# cSTER_Space_Robotic_Arm_Schematic.net
KiCad netlist of a schematic drawn in EAGLE
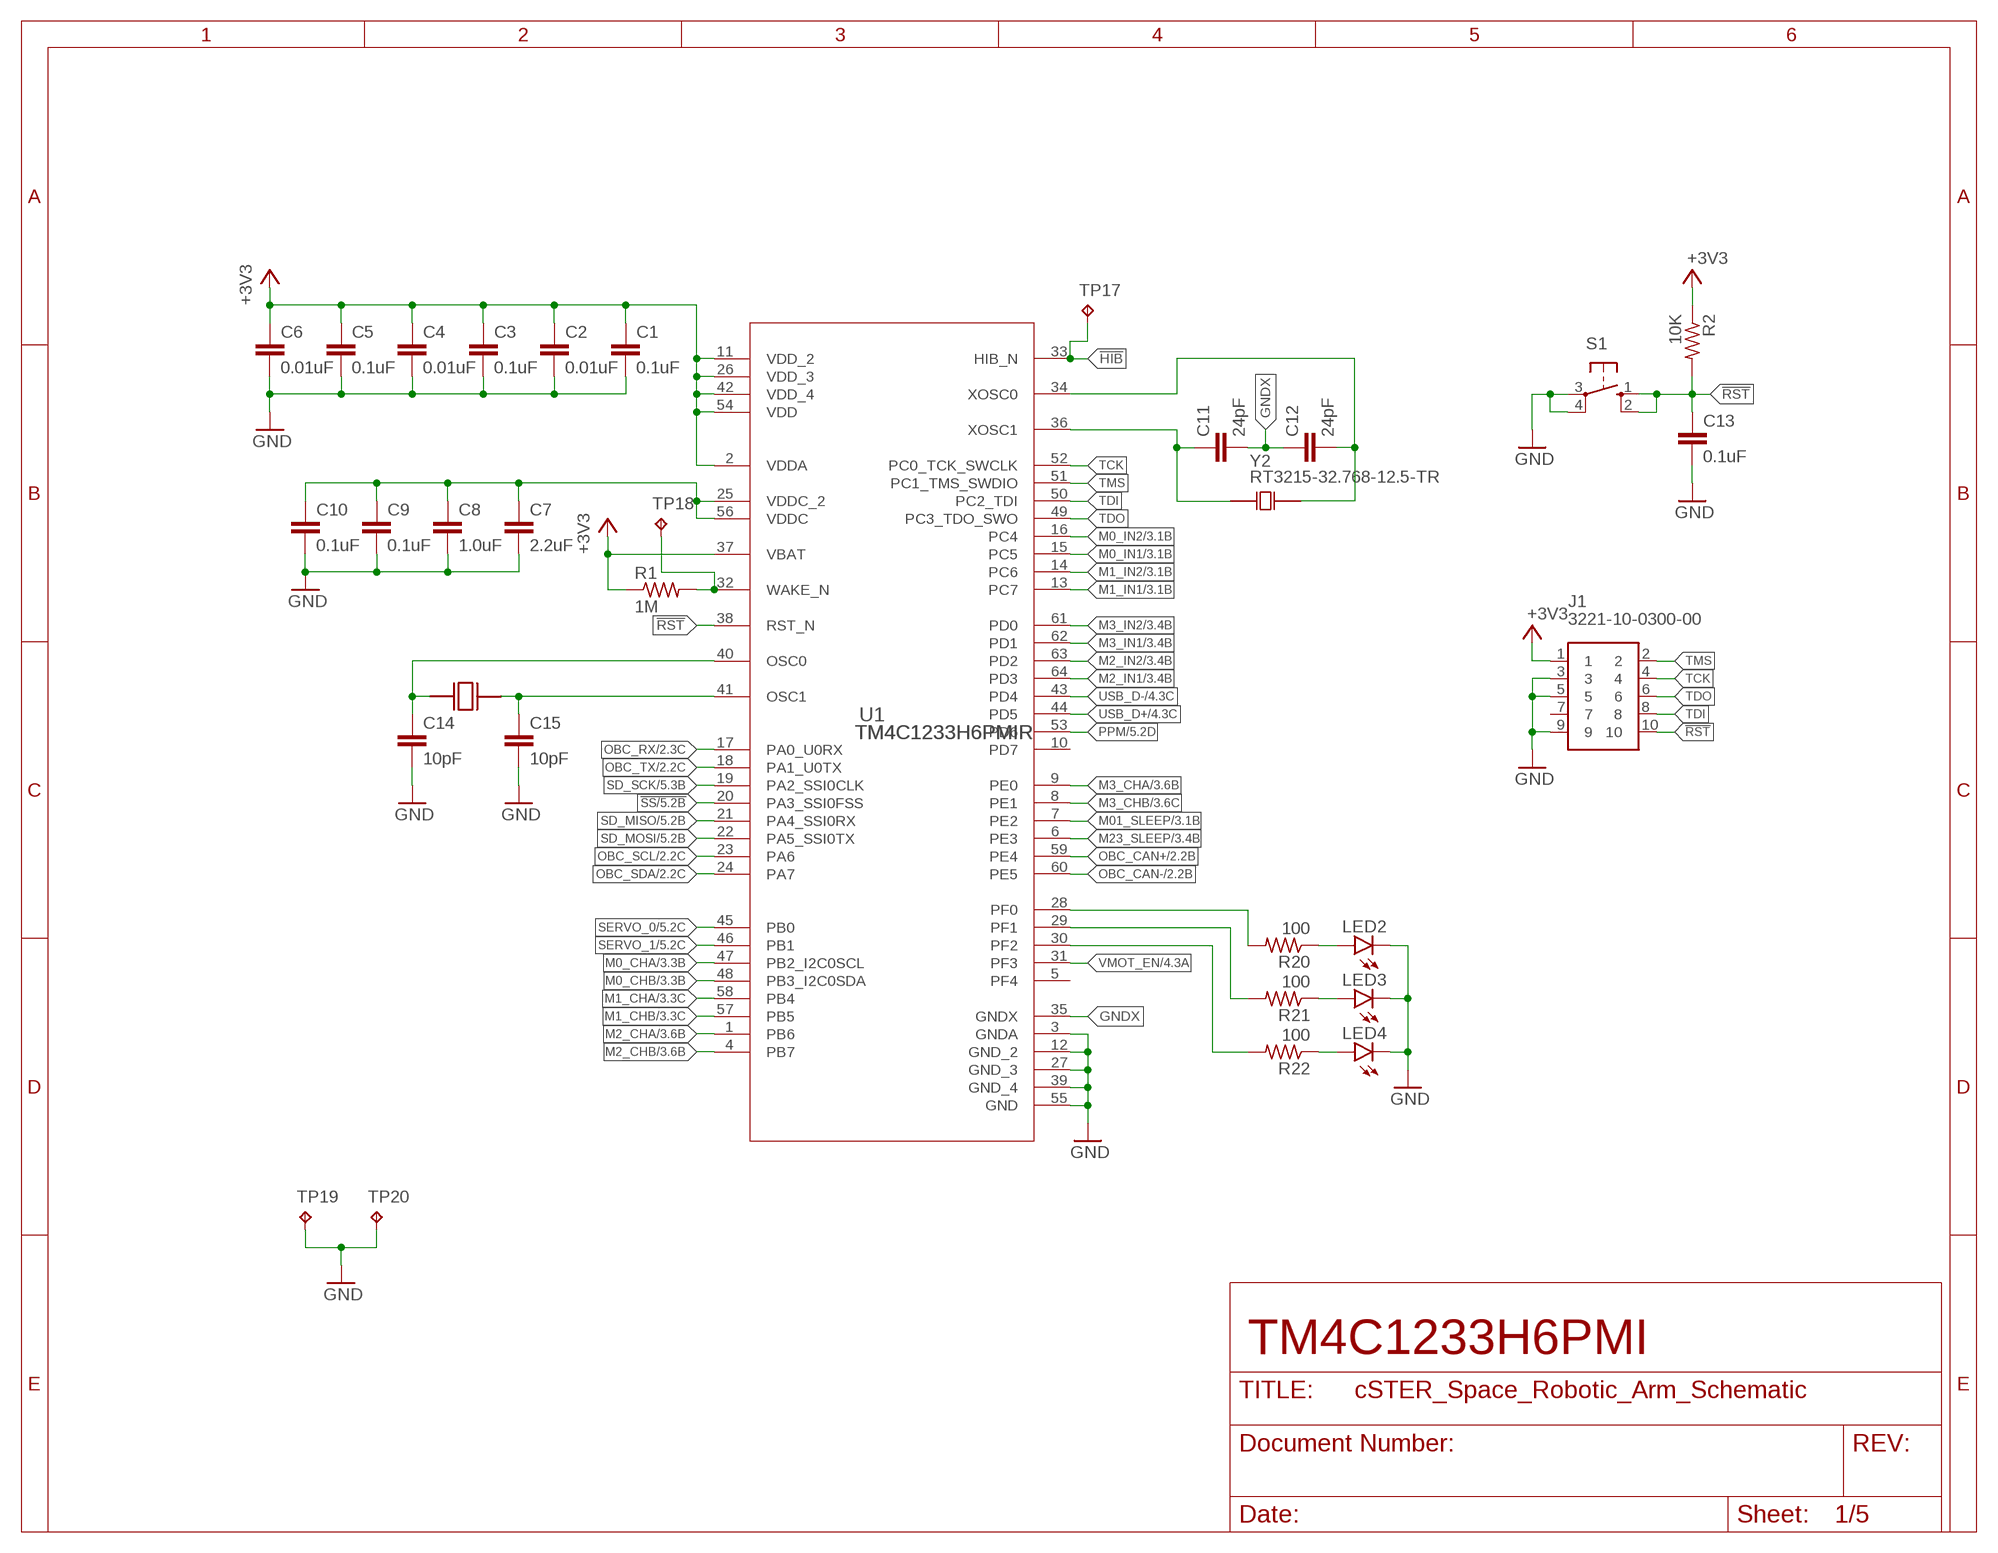
[diagram p0: schematic, sheet 1]
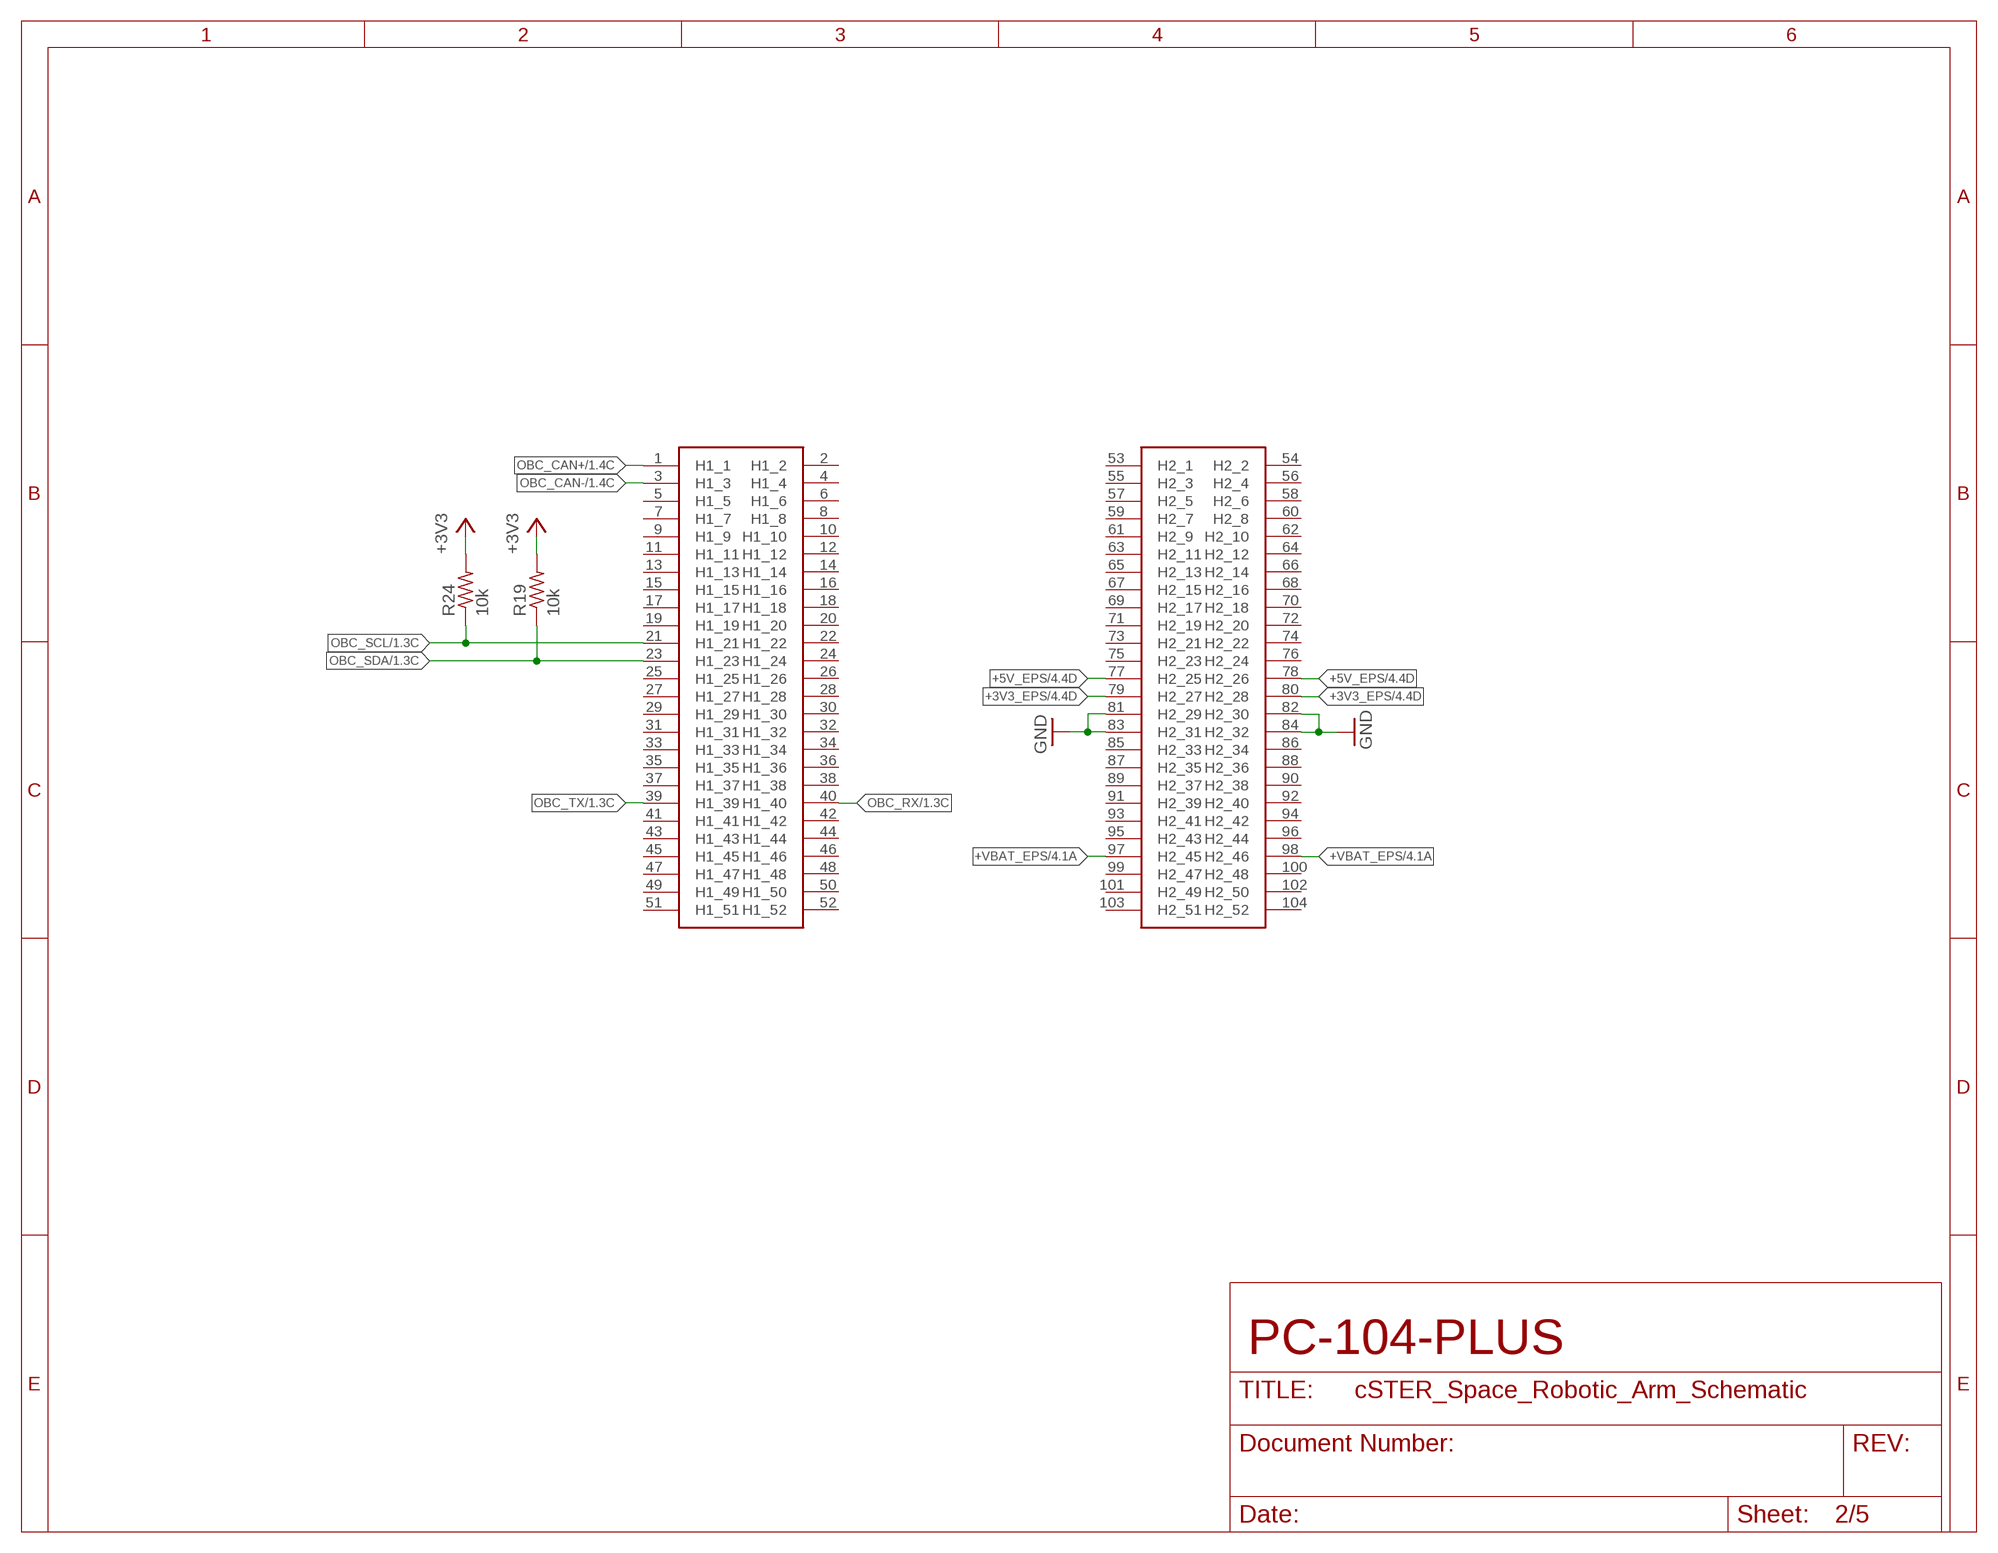
[diagram p1: schematic, sheet 2]
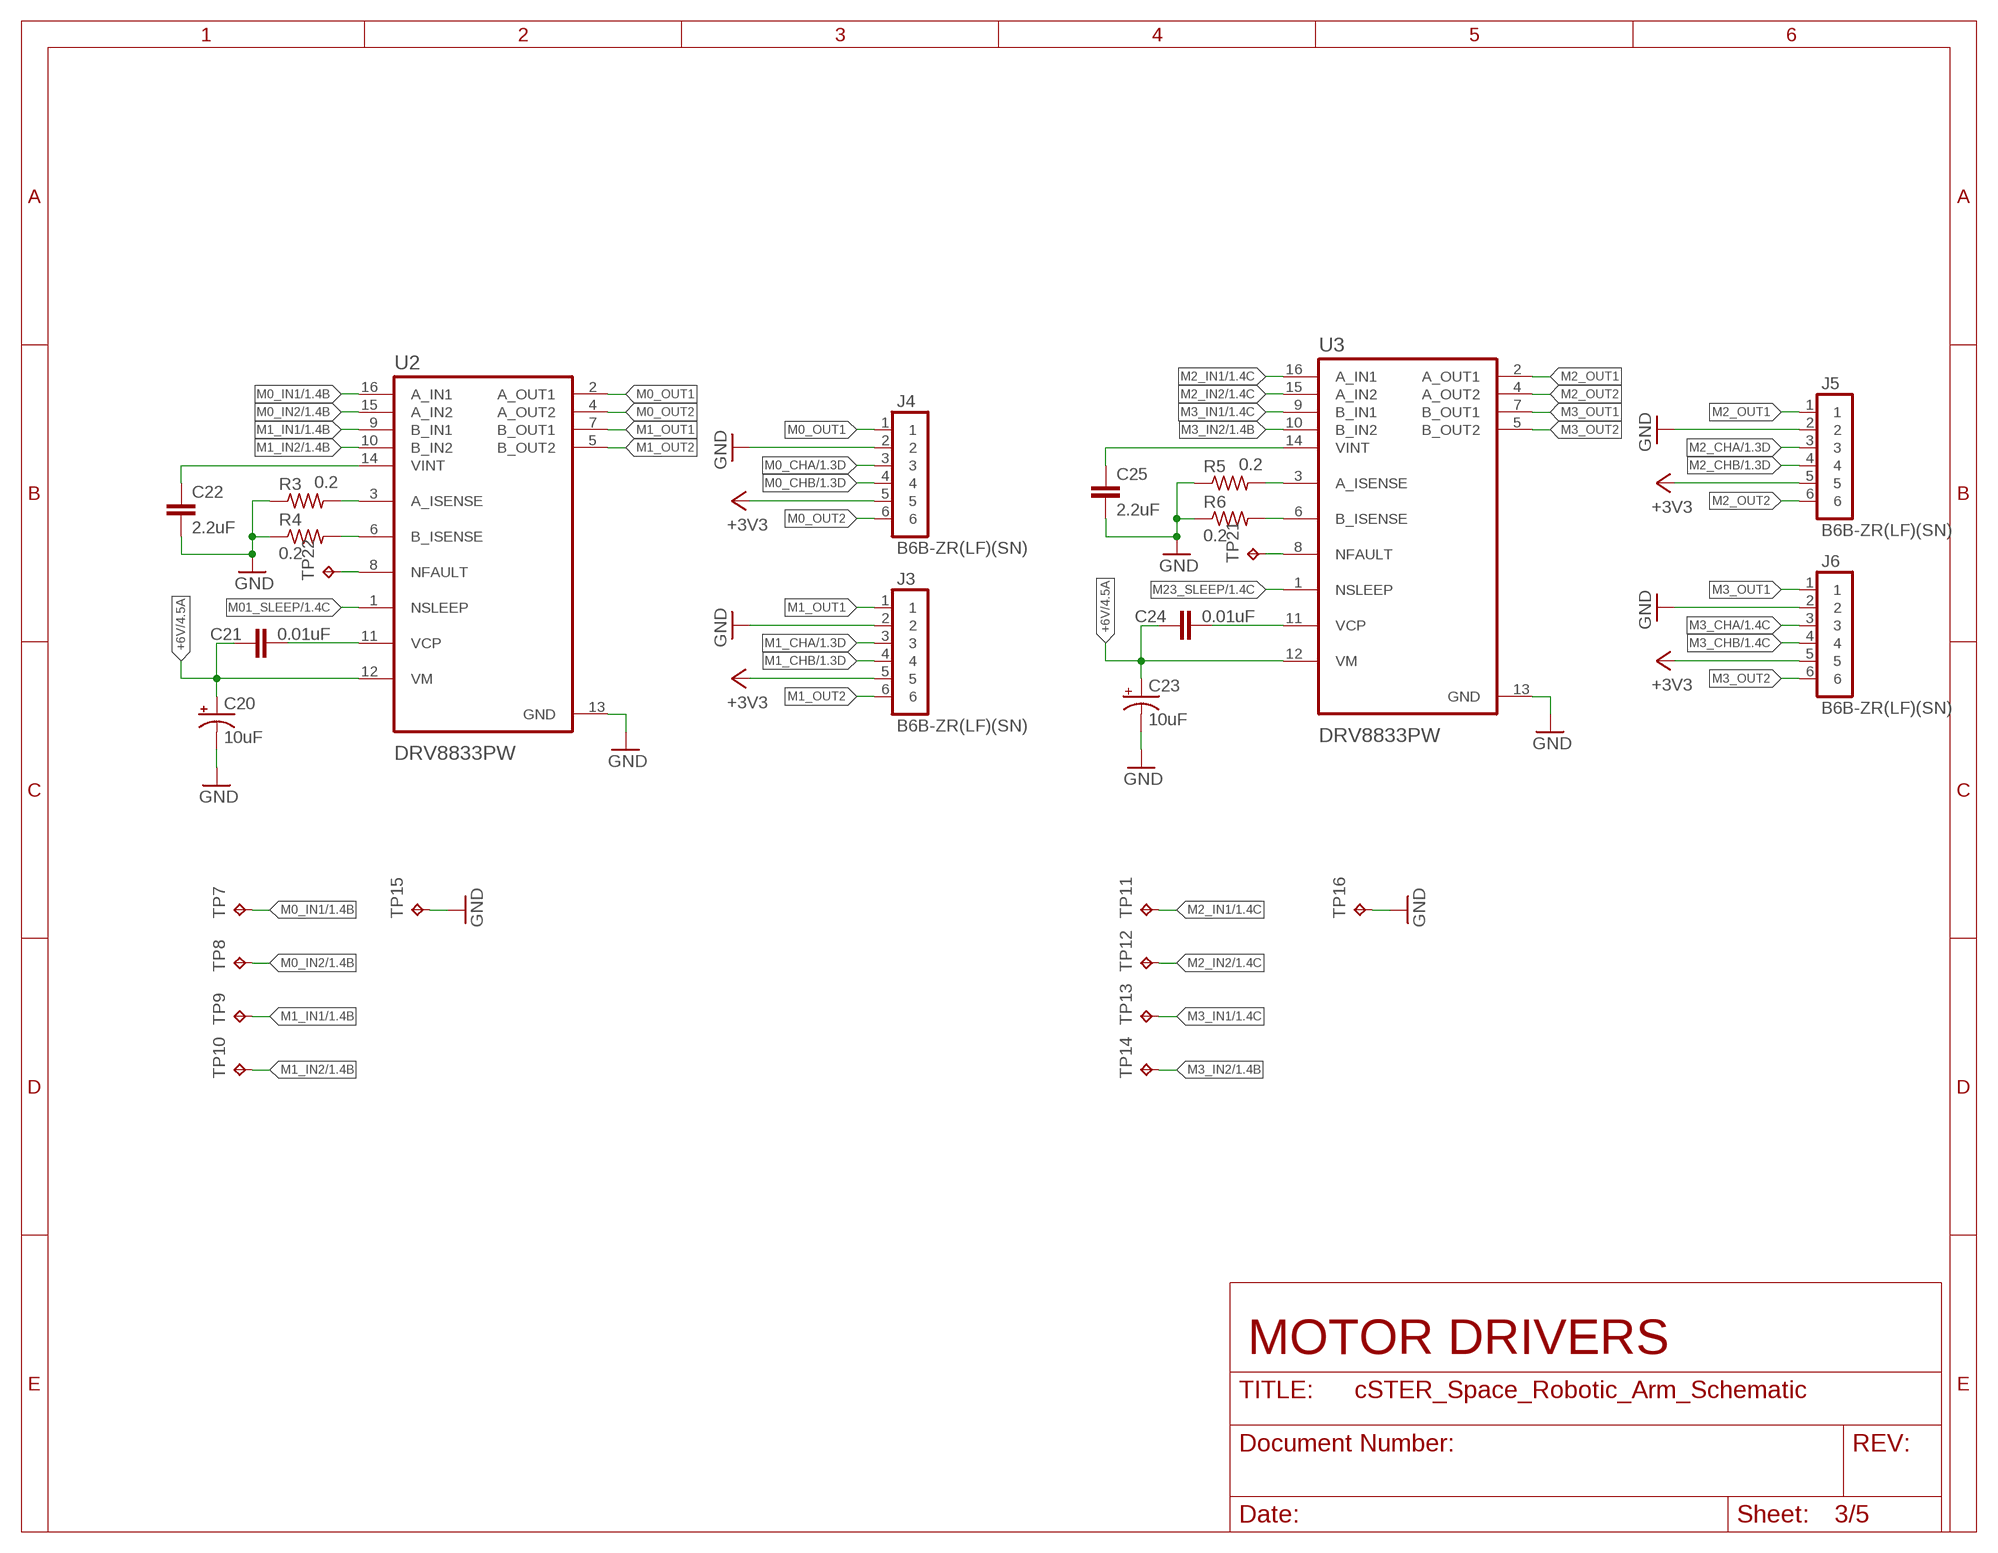
[diagram p2: schematic, sheet 3]
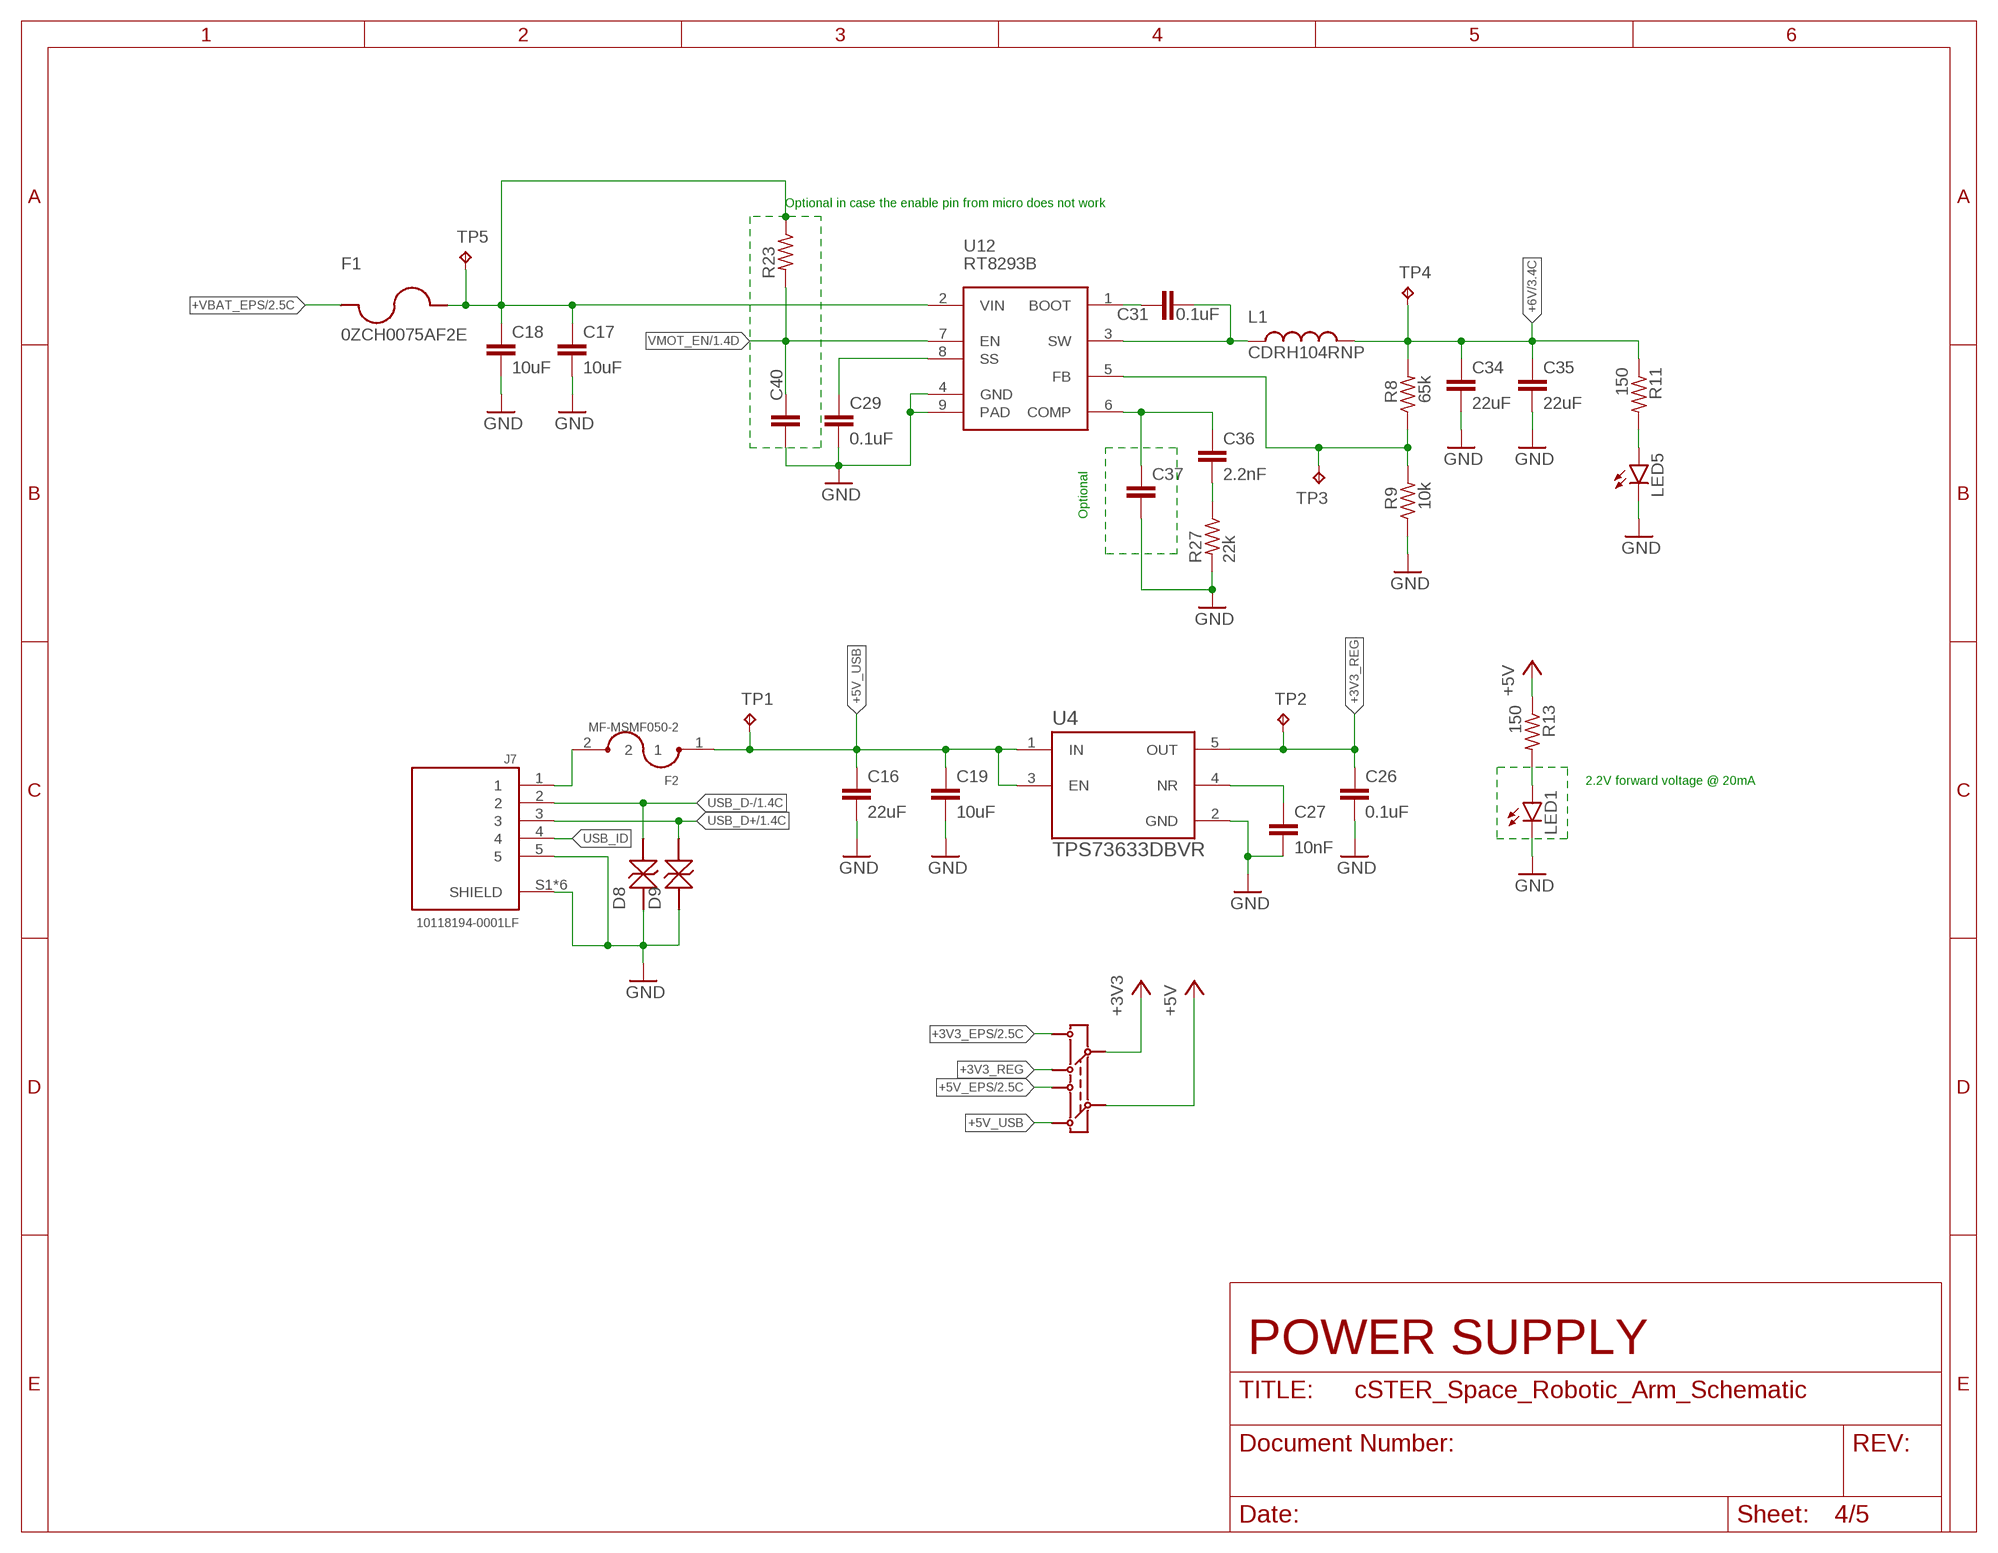
[diagram p3: schematic, sheet 4]
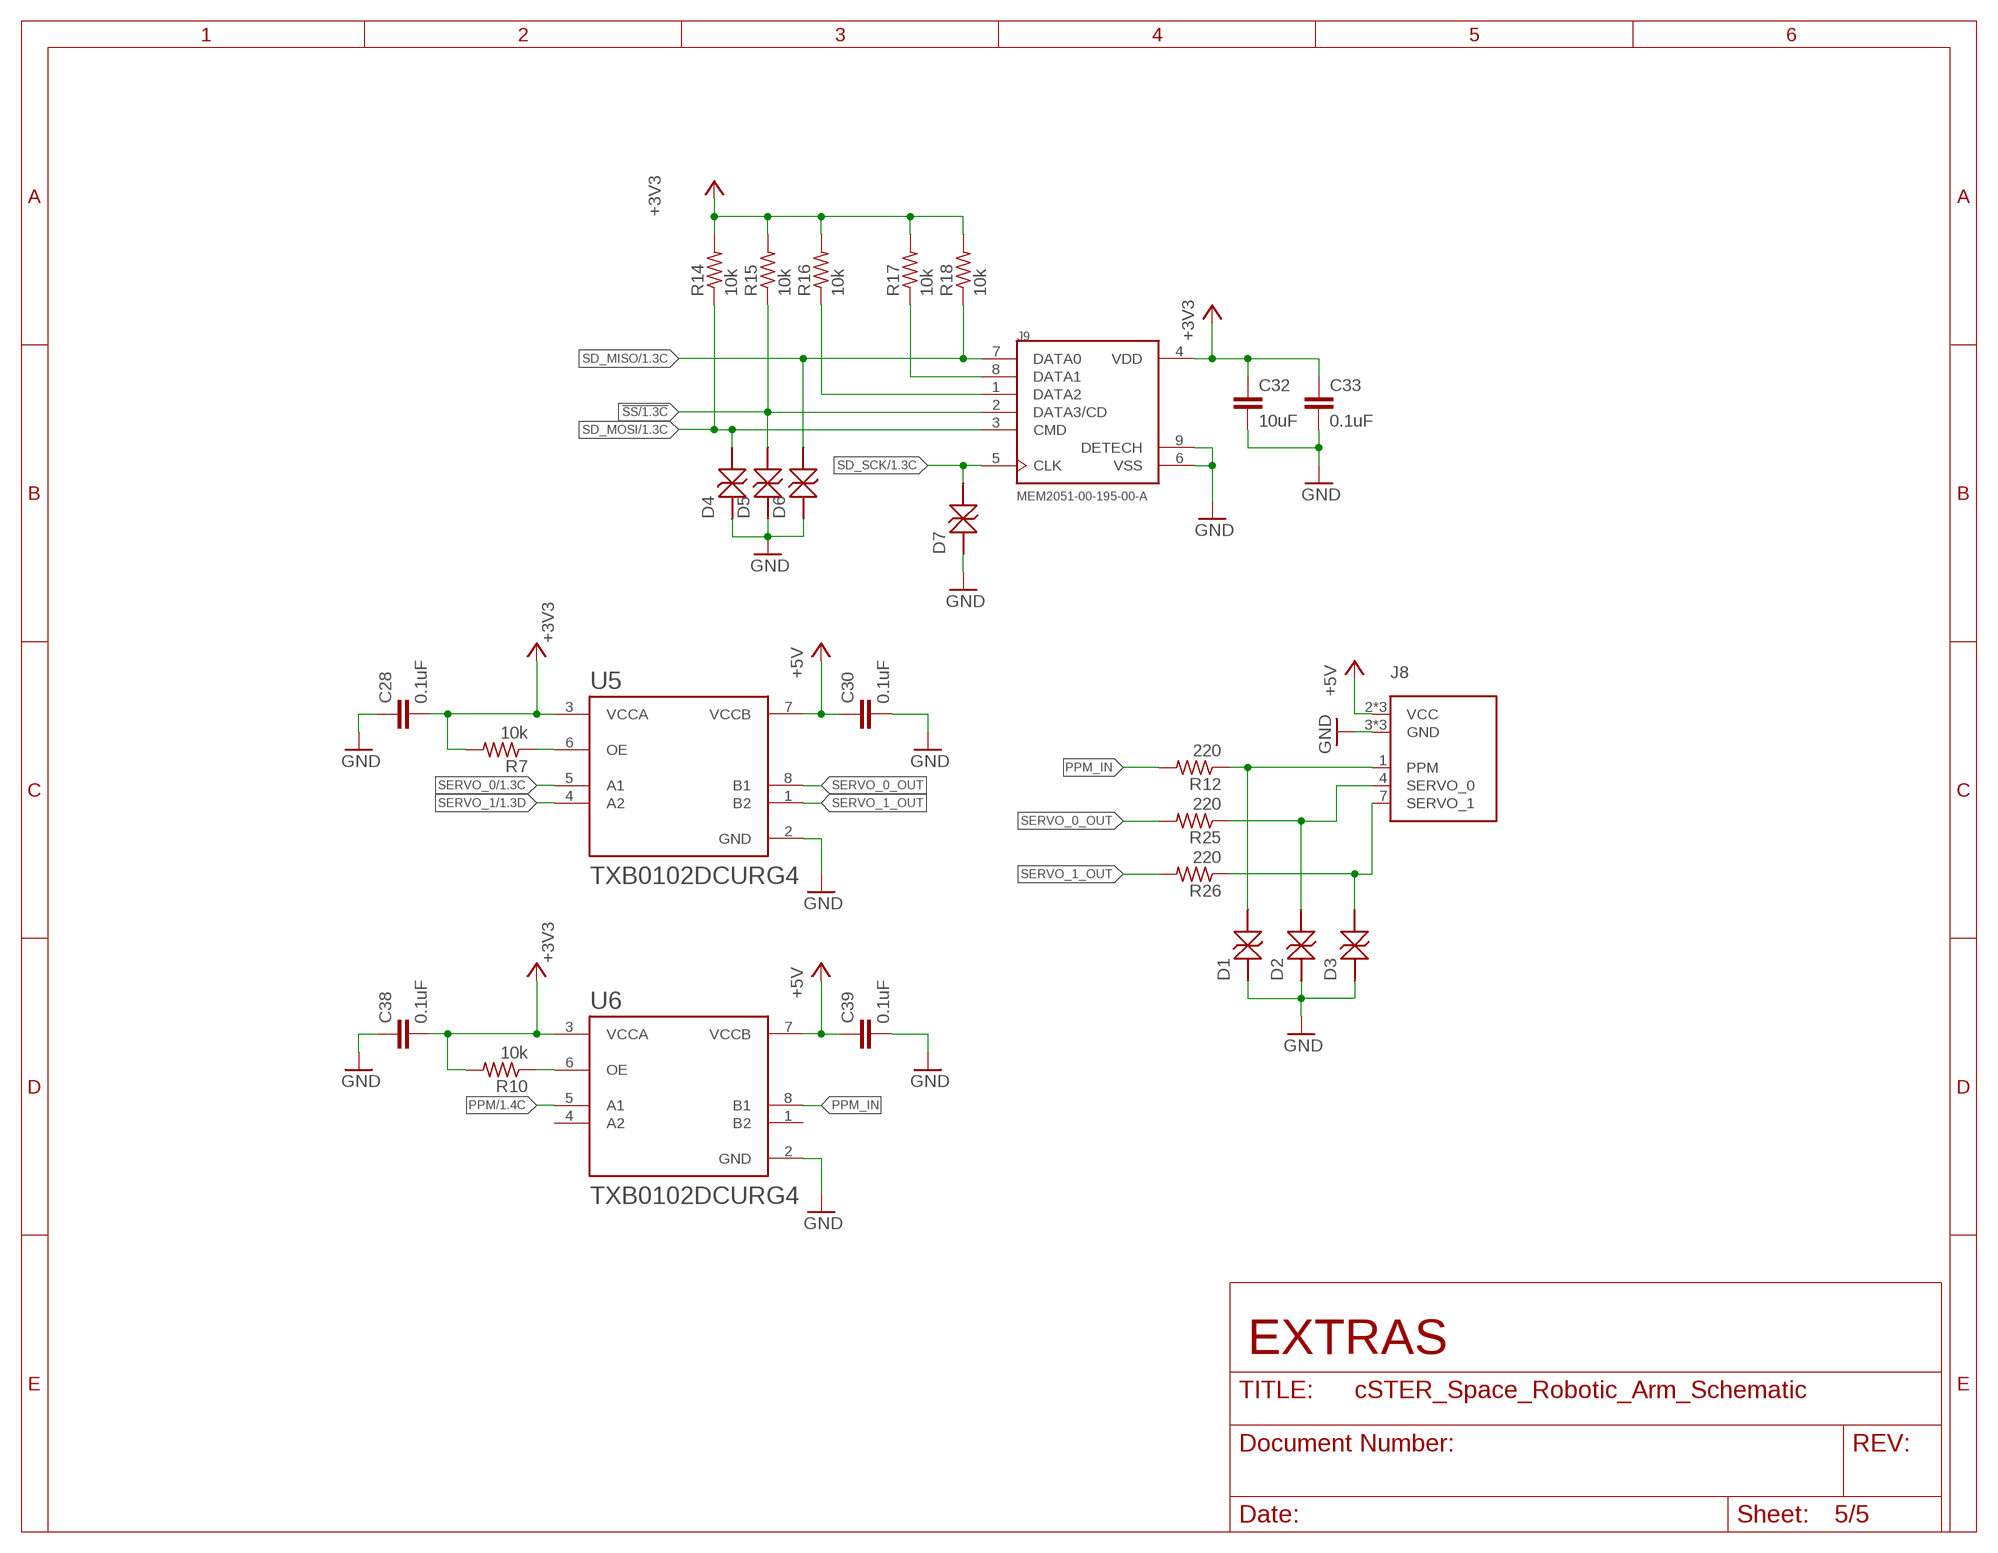
[diagram p4: schematic, sheet 5]

(export (version "E")
  (design (tool "Eeschema 10.0.6"))
  (components
    (comp (ref "C16")
      (value "22uF")
      (footprint "eagle-import:C1206")
      (libsource (lib "eagle-import") (part "C-EUC1206"))
    )
    (comp (ref "C17")
      (value "10uF")
      (footprint "eagle-import:C1206")
      (libsource (lib "eagle-import") (part "C-EUC1206"))
    )
    (comp (ref "C18")
      (value "10uF")
      (footprint "eagle-import:C1206")
      (libsource (lib "eagle-import") (part "C-EUC1206"))
    )
    (comp (ref "C19")
      (value "10uF")
      (footprint "eagle-import:C0603")
      (libsource (lib "eagle-import") (part "C-EUC0603"))
    )
    (comp (ref "C26")
      (value "0.1uF")
      (footprint "eagle-import:C0603")
      (libsource (lib "eagle-import") (part "C-EUC0603"))
    )
    (comp (ref "C27")
      (value "10nF")
      (footprint "eagle-import:C0603")
      (libsource (lib "eagle-import") (part "C-EUC0603"))
    )
    (comp (ref "C29")
      (value "0.1uF")
      (footprint "eagle-import:C0603")
      (libsource (lib "eagle-import") (part "C-EUC0603"))
    )
    (comp (ref "C31")
      (value "0.1uF")
      (footprint "eagle-import:C0603")
      (libsource (lib "eagle-import") (part "C-EUC0603"))
    )
    (comp (ref "C34")
      (value "22uF")
      (footprint "eagle-import:C1206")
      (libsource (lib "eagle-import") (part "C-EUC1206"))
    )
    (comp (ref "C35")
      (value "22uF")
      (footprint "eagle-import:C1206")
      (libsource (lib "eagle-import") (part "C-EUC1206"))
    )
    (comp (ref "C36")
      (value "2.2nF")
      (footprint "eagle-import:C0603")
      (libsource (lib "eagle-import") (part "C-EUC0603"))
    )
    (comp (ref "C37")
      (value "C-EUC0603")
      (footprint "eagle-import:C0603")
      (libsource (lib "eagle-import") (part "C-EUC0603"))
    )
    (comp (ref "C40")
      (value "C-EUC0603")
      (footprint "eagle-import:C0603")
      (libsource (lib "eagle-import") (part "C-EUC0603"))
    )
    (comp (ref "D8")
      (value "CPDQC5V0R")
      (footprint "eagle-import:CPDQC5V0R")
      (libsource (lib "eagle-import") (part "CPDQC5V0R"))
    )
    (comp (ref "D9")
      (value "CPDQC5V0R")
      (footprint "eagle-import:CPDQC5V0R")
      (libsource (lib "eagle-import") (part "CPDQC5V0R"))
    )
    (comp (ref "F1")
      (value "0ZCH0075AF2E")
      (footprint "eagle-import:0ZCH0075AF2E")
      (libsource (lib "eagle-import") (part "0ZCH0075AF2E"))
    )
    (comp (ref "F2")
      (value "MF-MSMF050-2")
      (footprint "eagle-import:FUSM4632X85")
      (fields (field (name "DIGI-KEY_PART_NUMBER") "MF-MSMF050-2CT-ND") (field (name "MF") "Bourns"))
      (libsource (lib "eagle-import") (part "MF-MSMF050-2"))
    )
    (comp (ref "J7")
      (value "10118194-0001LF")
      (footprint "eagle-import:AMPHENOL_10118194-0001LF")
      (fields (field (name "DIGI-KEY_PART_NUMBER") "609-4618-1-ND") (field (name "MF") "Amphenol ICC (FCI)"))
      (libsource (lib "eagle-import") (part "10118194-0001LF"))
    )
    (comp (ref "L1")
      (value "CDRH104RNP")
      (footprint "eagle-import:CDRH104RNP")
      (libsource (lib "eagle-import") (part "CDRH104RNP"))
    )
    (comp (ref "LED1")
      (value "LEDCHIPLED_0805")
      (footprint "eagle-import:CHIPLED_0805")
      (libsource (lib "eagle-import") (part "LEDCHIPLED_0805"))
    )
    (comp (ref "LED5")
      (value "LEDCHIPLED_0805")
      (footprint "eagle-import:CHIPLED_0805")
      (libsource (lib "eagle-import") (part "LEDCHIPLED_0805"))
    )
    (comp (ref "R8")
      (value "65k")
      (footprint "eagle-import:R0603")
      (libsource (lib "eagle-import") (part "R-US_R0603"))
    )
    (comp (ref "R9")
      (value "10k")
      (footprint "eagle-import:R0603")
      (libsource (lib "eagle-import") (part "R-US_R0603"))
    )
    (comp (ref "R11")
      (value "150")
      (footprint "eagle-import:R0603")
      (libsource (lib "eagle-import") (part "R-US_R0603"))
    )
    (comp (ref "R13")
      (value "150")
      (footprint "eagle-import:R0603")
      (libsource (lib "eagle-import") (part "R-US_R0603"))
    )
    (comp (ref "R23")
      (value "R-US_R0603")
      (footprint "eagle-import:R0603")
      (libsource (lib "eagle-import") (part "R-US_R0603"))
    )
    (comp (ref "R27")
      (value "22k")
      (footprint "eagle-import:R0603")
      (libsource (lib "eagle-import") (part "R-US_R0603"))
    )
    (comp (ref "TP1")
      (value "TPPAD1-13")
      (footprint "eagle-import:P1-13")
      (libsource (lib "eagle-import") (part "TPPAD1-13"))
    )
    (comp (ref "TP2")
      (value "TPPAD1-13")
      (footprint "eagle-import:P1-13")
      (libsource (lib "eagle-import") (part "TPPAD1-13"))
    )
    (comp (ref "TP3")
      (value "TPPAD1-13")
      (footprint "eagle-import:P1-13")
      (libsource (lib "eagle-import") (part "TPPAD1-13"))
    )
    (comp (ref "TP4")
      (value "TPPAD1-13")
      (footprint "eagle-import:P1-13")
      (libsource (lib "eagle-import") (part "TPPAD1-13"))
    )
    (comp (ref "TP5")
      (value "TPPAD1-13")
      (footprint "eagle-import:P1-13")
      (libsource (lib "eagle-import") (part "TPPAD1-13"))
    )
    (comp (ref "U$1")
      (value "JS202011CQN")
      (footprint "eagle-import:JS202011CQN")
      (libsource (lib "eagle-import") (part "JS202011CQN"))
    )
    (comp (ref "U4")
      (value "TPS73633DBVR")
      (footprint "eagle-import:SOT95P280X145-5N")
      (fields (field (name "DIGI-KEY_PART_NUMBER") "296-27064-1-ND") (field (name "MF") "Texas Instruments"))
      (libsource (lib "eagle-import") (part "TPS73633DBVR"))
    )
    (comp (ref "U12")
      (value "RT8293B")
      (footprint "eagle-import:RT8293B")
      (libsource (lib "eagle-import") (part "RT8293B"))
    )
    (comp (ref "C20")
      (value "10uF")
      (footprint "eagle-import:CT3216")
      (libsource (lib "eagle-import") (part "CPOL-USCT3216"))
    )
    (comp (ref "C21")
      (value "0.01uF")
      (footprint "eagle-import:C0805")
      (libsource (lib "eagle-import") (part "C-EUC0805"))
    )
    (comp (ref "C22")
      (value "2.2uF")
      (footprint "eagle-import:C0603")
      (libsource (lib "eagle-import") (part "C-EUC0603"))
    )
    (comp (ref "C23")
      (value "10uF")
      (footprint "eagle-import:CT3216")
      (libsource (lib "eagle-import") (part "CPOL-USCT3216"))
    )
    (comp (ref "C24")
      (value "0.01uF")
      (footprint "eagle-import:C0805")
      (libsource (lib "eagle-import") (part "C-EUC0805"))
    )
    (comp (ref "C25")
      (value "2.2uF")
      (footprint "eagle-import:C0603")
      (libsource (lib "eagle-import") (part "C-EUC0603"))
    )
    (comp (ref "J3")
      (value "B6B-ZR(LF)(SN)")
      (footprint "eagle-import:JST_B6B-ZR(LF)(SN)")
      (fields (field (name "DIGI-KEY_PART_NUMBER") "455-1661-ND") (field (name "MF") "JST Sales"))
      (libsource (lib "eagle-import") (part "B6B-ZR(LF)(SN)"))
    )
    (comp (ref "J4")
      (value "B6B-ZR(LF)(SN)")
      (footprint "eagle-import:JST_B6B-ZR(LF)(SN)")
      (fields (field (name "DIGI-KEY_PART_NUMBER") "455-1661-ND") (field (name "MF") "JST Sales"))
      (libsource (lib "eagle-import") (part "B6B-ZR(LF)(SN)"))
    )
    (comp (ref "J5")
      (value "B6B-ZR(LF)(SN)")
      (footprint "eagle-import:JST_B6B-ZR(LF)(SN)")
      (fields (field (name "DIGI-KEY_PART_NUMBER") "455-1661-ND") (field (name "MF") "JST Sales"))
      (libsource (lib "eagle-import") (part "B6B-ZR(LF)(SN)"))
    )
    (comp (ref "J6")
      (value "B6B-ZR(LF)(SN)")
      (footprint "eagle-import:JST_B6B-ZR(LF)(SN)")
      (fields (field (name "DIGI-KEY_PART_NUMBER") "455-1661-ND") (field (name "MF") "JST Sales"))
      (libsource (lib "eagle-import") (part "B6B-ZR(LF)(SN)"))
    )
    (comp (ref "R3")
      (value "0.2")
      (footprint "eagle-import:R1206")
      (libsource (lib "eagle-import") (part "R-US_R1206"))
    )
    (comp (ref "R4")
      (value "0.2")
      (footprint "eagle-import:R1206")
      (libsource (lib "eagle-import") (part "R-US_R1206"))
    )
    (comp (ref "R5")
      (value "0.2")
      (footprint "eagle-import:R1206")
      (libsource (lib "eagle-import") (part "R-US_R1206"))
    )
    (comp (ref "R6")
      (value "0.2")
      (footprint "eagle-import:R1206")
      (libsource (lib "eagle-import") (part "R-US_R1206"))
    )
    (comp (ref "TP7")
      (value "TPPAD1-13")
      (footprint "eagle-import:P1-13")
      (libsource (lib "eagle-import") (part "TPPAD1-13"))
    )
    (comp (ref "TP8")
      (value "TPPAD1-13")
      (footprint "eagle-import:P1-13")
      (libsource (lib "eagle-import") (part "TPPAD1-13"))
    )
    (comp (ref "TP9")
      (value "TPPAD1-13")
      (footprint "eagle-import:P1-13")
      (libsource (lib "eagle-import") (part "TPPAD1-13"))
    )
    (comp (ref "TP10")
      (value "TPPAD1-13")
      (footprint "eagle-import:P1-13")
      (libsource (lib "eagle-import") (part "TPPAD1-13"))
    )
    (comp (ref "TP11")
      (value "TPPAD1-13")
      (footprint "eagle-import:P1-13")
      (libsource (lib "eagle-import") (part "TPPAD1-13"))
    )
    (comp (ref "TP12")
      (value "TPPAD1-13")
      (footprint "eagle-import:P1-13")
      (libsource (lib "eagle-import") (part "TPPAD1-13"))
    )
    (comp (ref "TP13")
      (value "TPPAD1-13")
      (footprint "eagle-import:P1-13")
      (libsource (lib "eagle-import") (part "TPPAD1-13"))
    )
    (comp (ref "TP14")
      (value "TPPAD1-13")
      (footprint "eagle-import:P1-13")
      (libsource (lib "eagle-import") (part "TPPAD1-13"))
    )
    (comp (ref "TP15")
      (value "TPPAD1-13")
      (footprint "eagle-import:P1-13")
      (libsource (lib "eagle-import") (part "TPPAD1-13"))
    )
    (comp (ref "TP16")
      (value "TPPAD1-13")
      (footprint "eagle-import:P1-13")
      (libsource (lib "eagle-import") (part "TPPAD1-13"))
    )
    (comp (ref "TP21")
      (value "TPPAD1-13")
      (footprint "eagle-import:P1-13")
      (libsource (lib "eagle-import") (part "TPPAD1-13"))
    )
    (comp (ref "TP22")
      (value "TPPAD1-13")
      (footprint "eagle-import:P1-13")
      (libsource (lib "eagle-import") (part "TPPAD1-13"))
    )
    (comp (ref "U2")
      (value "DRV8833PW")
      (footprint "eagle-import:SOP65P640X120-16N")
      (fields (field (name "DIGI-KEY_PART_NUMBER") "296-29394-5-ND") (field (name "MF") "Texas Instruments"))
      (libsource (lib "eagle-import") (part "DRV8833PW"))
    )
    (comp (ref "U3")
      (value "DRV8833PW")
      (footprint "eagle-import:SOP65P640X120-16N")
      (fields (field (name "DIGI-KEY_PART_NUMBER") "296-29394-5-ND") (field (name "MF") "Texas Instruments"))
      (libsource (lib "eagle-import") (part "DRV8833PW"))
    )
    (comp (ref "C28")
      (value "0.1uF")
      (footprint "eagle-import:C0402K")
      (libsource (lib "eagle-import") (part "C-EUC0402K"))
    )
    (comp (ref "C30")
      (value "0.1uF")
      (footprint "eagle-import:C0402K")
      (libsource (lib "eagle-import") (part "C-EUC0402K"))
    )
    (comp (ref "C32")
      (value "10uF")
      (footprint "eagle-import:C0603")
      (libsource (lib "eagle-import") (part "C-EUC0603"))
    )
    (comp (ref "C33")
      (value "0.1uF")
      (footprint "eagle-import:C0603")
      (libsource (lib "eagle-import") (part "C-EUC0603"))
    )
    (comp (ref "C38")
      (value "0.1uF")
      (footprint "eagle-import:C0402K")
      (libsource (lib "eagle-import") (part "C-EUC0402K"))
    )
    (comp (ref "C39")
      (value "0.1uF")
      (footprint "eagle-import:C0402K")
      (libsource (lib "eagle-import") (part "C-EUC0402K"))
    )
    (comp (ref "D1")
      (value "CPDQC5V0R")
      (footprint "eagle-import:CPDQC5V0R")
      (libsource (lib "eagle-import") (part "CPDQC5V0R"))
    )
    (comp (ref "D2")
      (value "CPDQC5V0R")
      (footprint "eagle-import:CPDQC5V0R")
      (libsource (lib "eagle-import") (part "CPDQC5V0R"))
    )
    (comp (ref "D3")
      (value "CPDQC5V0R")
      (footprint "eagle-import:CPDQC5V0R")
      (libsource (lib "eagle-import") (part "CPDQC5V0R"))
    )
    (comp (ref "D4")
      (value "CPDQC5V0R")
      (footprint "eagle-import:CPDQC5V0R")
      (libsource (lib "eagle-import") (part "CPDQC5V0R"))
    )
    (comp (ref "D5")
      (value "CPDQC5V0R")
      (footprint "eagle-import:CPDQC5V0R")
      (libsource (lib "eagle-import") (part "CPDQC5V0R"))
    )
    (comp (ref "D6")
      (value "CPDQC5V0R")
      (footprint "eagle-import:CPDQC5V0R")
      (libsource (lib "eagle-import") (part "CPDQC5V0R"))
    )
    (comp (ref "D7")
      (value "CPDQC5V0R")
      (footprint "eagle-import:CPDQC5V0R")
      (libsource (lib "eagle-import") (part "CPDQC5V0R"))
    )
    (comp (ref "J8")
      (value "ROBOT_PORT")
      (footprint "eagle-import:ROBOT_PORT")
      (libsource (lib "eagle-import") (part "ROBOT_PORT"))
    )
    (comp (ref "J9")
      (value "MEM2051-00-195-00-A")
      (footprint "eagle-import:GCT_MEM2051-00-195-00-A")
      (fields (field (name "MF") "Global Connector Technology"))
      (libsource (lib "eagle-import") (part "MEM2051-00-195-00-A"))
    )
    (comp (ref "R7")
      (value "10k")
      (footprint "eagle-import:R0402")
      (libsource (lib "eagle-import") (part "R-US_R0402"))
    )
    (comp (ref "R10")
      (value "10k")
      (footprint "eagle-import:R0402")
      (libsource (lib "eagle-import") (part "R-US_R0402"))
    )
    (comp (ref "R12")
      (value "220")
      (footprint "eagle-import:R0603")
      (libsource (lib "eagle-import") (part "R-US_R0603"))
    )
    (comp (ref "R14")
      (value "10k")
      (footprint "eagle-import:R0603")
      (libsource (lib "eagle-import") (part "R-US_R0603"))
    )
    (comp (ref "R15")
      (value "10k")
      (footprint "eagle-import:R0603")
      (libsource (lib "eagle-import") (part "R-US_R0603"))
    )
    (comp (ref "R16")
      (value "10k")
      (footprint "eagle-import:R0603")
      (libsource (lib "eagle-import") (part "R-US_R0603"))
    )
    (comp (ref "R17")
      (value "10k")
      (footprint "eagle-import:R0603")
      (libsource (lib "eagle-import") (part "R-US_R0603"))
    )
    (comp (ref "R18")
      (value "10k")
      (footprint "eagle-import:R0603")
      (libsource (lib "eagle-import") (part "R-US_R0603"))
    )
    (comp (ref "R25")
      (value "220")
      (footprint "eagle-import:R0603")
      (libsource (lib "eagle-import") (part "R-US_R0603"))
    )
    (comp (ref "R26")
      (value "220")
      (footprint "eagle-import:R0603")
      (libsource (lib "eagle-import") (part "R-US_R0603"))
    )
    (comp (ref "U5")
      (value "TXB0102DCURG4")
      (footprint "eagle-import:SOP50P310X90-8N")
      (fields (field (name "DIGI-KEY_PART_NUMBER") "296-52836-2-ND") (field (name "MF") "Texas Instruments"))
      (libsource (lib "eagle-import") (part "TXB0102DCURG4"))
    )
    (comp (ref "U6")
      (value "TXB0102DCURG4")
      (footprint "eagle-import:SOP50P310X90-8N")
      (fields (field (name "DIGI-KEY_PART_NUMBER") "296-52836-2-ND") (field (name "MF") "Texas Instruments"))
      (libsource (lib "eagle-import") (part "TXB0102DCURG4"))
    )
    (comp (ref "C1")
      (value "0.1uF")
      (footprint "eagle-import:C0402K")
      (libsource (lib "eagle-import") (part "C-EUC0402K"))
    )
    (comp (ref "C2")
      (value "0.01uF")
      (footprint "eagle-import:C0402K")
      (libsource (lib "eagle-import") (part "C-EUC0402K"))
    )
    (comp (ref "C3")
      (value "0.1uF")
      (footprint "eagle-import:C0402K")
      (libsource (lib "eagle-import") (part "C-EUC0402K"))
    )
    (comp (ref "C4")
      (value "0.01uF")
      (footprint "eagle-import:C0402K")
      (libsource (lib "eagle-import") (part "C-EUC0402K"))
    )
    (comp (ref "C5")
      (value "0.1uF")
      (footprint "eagle-import:C0402K")
      (libsource (lib "eagle-import") (part "C-EUC0402K"))
    )
    (comp (ref "C6")
      (value "0.01uF")
      (footprint "eagle-import:C0402K")
      (libsource (lib "eagle-import") (part "C-EUC0402K"))
    )
    (comp (ref "C7")
      (value "2.2uF")
      (footprint "eagle-import:C0402K")
      (libsource (lib "eagle-import") (part "C-EUC0402K"))
    )
    (comp (ref "C8")
      (value "1.0uF")
      (footprint "eagle-import:C0402K")
      (libsource (lib "eagle-import") (part "C-EUC0402K"))
    )
    (comp (ref "C9")
      (value "0.1uF")
      (footprint "eagle-import:C0402K")
      (libsource (lib "eagle-import") (part "C-EUC0402K"))
    )
    (comp (ref "C10")
      (value "0.1uF")
      (footprint "eagle-import:C0402K")
      (libsource (lib "eagle-import") (part "C-EUC0402K"))
    )
    (comp (ref "C11")
      (value "24pF")
      (footprint "eagle-import:C0402K")
      (libsource (lib "eagle-import") (part "C-EUC0402K"))
    )
    (comp (ref "C12")
      (value "24pF")
      (footprint "eagle-import:C0402K")
      (libsource (lib "eagle-import") (part "C-EUC0402K"))
    )
    (comp (ref "C13")
      (value "0.1uF")
      (footprint "eagle-import:C0603")
      (libsource (lib "eagle-import") (part "C-EUC0603"))
    )
    (comp (ref "C14")
      (value "10pF")
      (footprint "eagle-import:C0402K")
      (libsource (lib "eagle-import") (part "C-EUC0402K"))
    )
    (comp (ref "C15")
      (value "10pF")
      (footprint "eagle-import:C0402K")
      (libsource (lib "eagle-import") (part "C-EUC0402K"))
    )
    (comp (ref "J1")
      (value "3221-10-0300-00")
      (footprint "eagle-import:3221-10-0300-00")
      (libsource (lib "eagle-import") (part "3221-10-0300-00"))
    )
    (comp (ref "LED2")
      (value "LEDCHIPLED_0805")
      (footprint "eagle-import:CHIPLED_0805")
      (libsource (lib "eagle-import") (part "LEDCHIPLED_0805"))
    )
    (comp (ref "LED3")
      (value "LEDCHIPLED_0805")
      (footprint "eagle-import:CHIPLED_0805")
      (libsource (lib "eagle-import") (part "LEDCHIPLED_0805"))
    )
    (comp (ref "LED4")
      (value "LEDCHIPLED_0805")
      (footprint "eagle-import:CHIPLED_0805")
      (libsource (lib "eagle-import") (part "LEDCHIPLED_0805"))
    )
    (comp (ref "R1")
      (value "1M")
      (footprint "eagle-import:R0402")
      (libsource (lib "eagle-import") (part "R-US_R0402"))
    )
    (comp (ref "R2")
      (value "10K")
      (footprint "eagle-import:R0603")
      (libsource (lib "eagle-import") (part "R-US_R0603"))
    )
    (comp (ref "R20")
      (value "100")
      (footprint "eagle-import:R0603")
      (libsource (lib "eagle-import") (part "R-US_R0603"))
    )
    (comp (ref "R21")
      (value "100")
      (footprint "eagle-import:R0603")
      (libsource (lib "eagle-import") (part "R-US_R0603"))
    )
    (comp (ref "R22")
      (value "100")
      (footprint "eagle-import:R0603")
      (libsource (lib "eagle-import") (part "R-US_R0603"))
    )
    (comp (ref "S1")
      (value "10-XX")
      (footprint "eagle-import:B3F-10XX")
      (fields (field (name "MPN") "B3F-1000"))
      (libsource (lib "eagle-import") (part "10-XX"))
    )
    (comp (ref "TP17")
      (value "TPPAD1-13")
      (footprint "eagle-import:P1-13")
      (libsource (lib "eagle-import") (part "TPPAD1-13"))
    )
    (comp (ref "TP18")
      (value "TPPAD1-13")
      (footprint "eagle-import:P1-13")
      (libsource (lib "eagle-import") (part "TPPAD1-13"))
    )
    (comp (ref "TP19")
      (value "TPPAD1-13")
      (footprint "eagle-import:P1-13")
      (libsource (lib "eagle-import") (part "TPPAD1-13"))
    )
    (comp (ref "TP20")
      (value "TPPAD1-13")
      (footprint "eagle-import:P1-13")
      (libsource (lib "eagle-import") (part "TPPAD1-13"))
    )
    (comp (ref "U1")
      (value "TM4C1233H6PMIR")
      (footprint "eagle-import:PM0064A_N")
      (fields (field (name "COPYRIGHT") "Copyright (C) 2021 Ultra Librarian. All rights reserved."))
      (libsource (lib "eagle-import") (part "TM4C1233H6PMIR"))
    )
    (comp (ref "Y1")
      (value "ECS-160-9-42-CKM-TR")
      (footprint "eagle-import:XTAL_ECS-160-9-42-CKM-TR")
      (fields (field (name "DIGI-KEY_PART_NUMBER") "XC1611CT-ND") (field (name "MF") "ECS Inc."))
      (libsource (lib "eagle-import") (part "ECS-160-9-42-CKM-TR"))
    )
    (comp (ref "Y2")
      (value "RT3215-32.768-12.5-TR")
      (footprint "eagle-import:RT3215-32.768-12.5-TR")
      (libsource (lib "eagle-import") (part "RT3215-32.768-12.5-TR"))
    )
    (comp (ref "J2")
      (value "PC-104-PLUS")
      (footprint "eagle-import:PC-104-PLUS")
      (libsource (lib "eagle-import") (part "PC-104-PLUS"))
    )
    (comp (ref "R19")
      (value "10k")
      (footprint "eagle-import:R0603")
      (libsource (lib "eagle-import") (part "R-US_R0603"))
    )
    (comp (ref "R24")
      (value "10k")
      (footprint "eagle-import:R0603")
      (libsource (lib "eagle-import") (part "R-US_R0603"))
    )
  )
  (nets
    (net (code "1") (name "+3V3") (class "Default")
      (node (ref "C1") (pin "1") (pinfunction "1_1") (pintype "passive"))
      (node (ref "C2") (pin "1") (pinfunction "1_1") (pintype "passive"))
      (node (ref "C28") (pin "2") (pinfunction "2_2") (pintype "passive"))
      (node (ref "C3") (pin "1") (pinfunction "1_1") (pintype "passive"))
      (node (ref "C32") (pin "1") (pinfunction "1_1") (pintype "passive"))
      (node (ref "C33") (pin "1") (pinfunction "1_1") (pintype "passive"))
      (node (ref "C38") (pin "2") (pinfunction "2_2") (pintype "passive"))
      (node (ref "C4") (pin "1") (pinfunction "1_1") (pintype "passive"))
      (node (ref "C5") (pin "1") (pinfunction "1_1") (pintype "passive"))
      (node (ref "C6") (pin "1") (pinfunction "1_1") (pintype "passive"))
      (node (ref "J1") (pin "1") (pinfunction "1_1") (pintype "bidirectional"))
      (node (ref "J3") (pin "5") (pinfunction "5_5") (pintype "passive"))
      (node (ref "J4") (pin "5") (pinfunction "5_5") (pintype "passive"))
      (node (ref "J5") (pin "5") (pinfunction "5_5") (pintype "passive"))
      (node (ref "J6") (pin "5") (pinfunction "5_5") (pintype "passive"))
      (node (ref "J9") (pin "4") (pinfunction "VDD_4") (pintype "power_in"))
      (node (ref "R1") (pin "1") (pinfunction "1_1") (pintype "passive"))
      (node (ref "R10") (pin "2") (pinfunction "2_2") (pintype "passive"))
      (node (ref "R14") (pin "2") (pinfunction "2_2") (pintype "passive"))
      (node (ref "R15") (pin "2") (pinfunction "2_2") (pintype "passive"))
      (node (ref "R16") (pin "2") (pinfunction "2_2") (pintype "passive"))
      (node (ref "R17") (pin "2") (pinfunction "2_2") (pintype "passive"))
      (node (ref "R18") (pin "2") (pinfunction "2_2") (pintype "passive"))
      (node (ref "R19") (pin "2") (pinfunction "2_2") (pintype "passive"))
      (node (ref "R2") (pin "1") (pinfunction "1_1") (pintype "passive"))
      (node (ref "R24") (pin "2") (pinfunction "2_2") (pintype "passive"))
      (node (ref "R7") (pin "2") (pinfunction "2_2") (pintype "passive"))
      (node (ref "U$1") (pin "5") (pinfunction "5_5") (pintype "passive"))
      (node (ref "U1") (pin "11") (pinfunction "VDD_2_11") (pintype "power_in"))
      (node (ref "U1") (pin "2") (pinfunction "VDDA_2") (pintype "power_in"))
      (node (ref "U1") (pin "26") (pinfunction "VDD_3_26") (pintype "power_in"))
      (node (ref "U1") (pin "37") (pinfunction "VBAT_37") (pintype "power_in"))
      (node (ref "U1") (pin "42") (pinfunction "VDD_4_42") (pintype "power_in"))
      (node (ref "U1") (pin "54") (pinfunction "VDD_54") (pintype "power_in"))
      (node (ref "U5") (pin "3") (pinfunction "VCCA_3") (pintype "power_in"))
      (node (ref "U6") (pin "3") (pinfunction "VCCA_3") (pintype "power_in"))
    )
    (net (code "2") (name "+3V3_EPS") (class "Default")
      (node (ref "J2") (pin "79") (pinfunction "H2_27_79") (pintype "bidirectional"))
      (node (ref "J2") (pin "80") (pinfunction "H2_28_80") (pintype "bidirectional"))
      (node (ref "U$1") (pin "6") (pinfunction "6_6") (pintype "passive"))
    )
    (net (code "3") (name "+3V3_REG") (class "Default")
      (node (ref "C26") (pin "1") (pinfunction "1_1") (pintype "passive"))
      (node (ref "TP2") (pin "TP") (pinfunction "TP_TP") (pintype "input"))
      (node (ref "U$1") (pin "4") (pinfunction "4_4") (pintype "passive"))
      (node (ref "U4") (pin "5") (pinfunction "OUT_5") (pintype "output"))
    )
    (net (code "4") (name "+5V") (class "Default")
      (node (ref "C30") (pin "1") (pinfunction "1_1") (pintype "passive"))
      (node (ref "C39") (pin "1") (pinfunction "1_1") (pintype "passive"))
      (node (ref "J8") (pin "2") (pinfunction "VCC_2") (pintype "passive"))
      (node (ref "J8") (pin "5") (pinfunction "VCC_5") (pintype "passive"))
      (node (ref "J8") (pin "8") (pinfunction "VCC_8") (pintype "passive"))
      (node (ref "R13") (pin "1") (pinfunction "1_1") (pintype "passive"))
      (node (ref "U$1") (pin "2") (pinfunction "2_2") (pintype "passive"))
      (node (ref "U5") (pin "7") (pinfunction "VCCB_7") (pintype "power_in"))
      (node (ref "U6") (pin "7") (pinfunction "VCCB_7") (pintype "power_in"))
    )
    (net (code "5") (name "+5V_EPS") (class "Default")
      (node (ref "J2") (pin "77") (pinfunction "H2_25_77") (pintype "bidirectional"))
      (node (ref "J2") (pin "78") (pinfunction "H2_26_78") (pintype "bidirectional"))
      (node (ref "U$1") (pin "3") (pinfunction "3_3") (pintype "passive"))
    )
    (net (code "6") (name "+5V_USB") (class "Default")
      (node (ref "C16") (pin "1") (pinfunction "1_1") (pintype "passive"))
      (node (ref "C19") (pin "1") (pinfunction "1_1") (pintype "passive"))
      (node (ref "F2") (pin "1") (pinfunction "1_1") (pintype "passive"))
      (node (ref "TP1") (pin "TP") (pinfunction "TP_TP") (pintype "input"))
      (node (ref "U$1") (pin "1") (pinfunction "1_1") (pintype "passive"))
      (node (ref "U4") (pin "1") (pinfunction "IN_1") (pintype "input"))
      (node (ref "U4") (pin "3") (pinfunction "EN_3") (pintype "input"))
    )
    (net (code "7") (name "+6V") (class "Default")
      (node (ref "C20") (pin "+") (pinfunction "+_+") (pintype "passive"))
      (node (ref "C21") (pin "1") (pinfunction "1_1") (pintype "passive"))
      (node (ref "C23") (pin "+") (pinfunction "+_+") (pintype "passive"))
      (node (ref "C24") (pin "1") (pinfunction "1_1") (pintype "passive"))
      (node (ref "C34") (pin "1") (pinfunction "1_1") (pintype "passive"))
      (node (ref "C35") (pin "1") (pinfunction "1_1") (pintype "passive"))
      (node (ref "L1") (pin "2") (pinfunction "2_2") (pintype "bidirectional"))
      (node (ref "R11") (pin "1") (pinfunction "1_1") (pintype "passive"))
      (node (ref "R8") (pin "2") (pinfunction "2_2") (pintype "passive"))
      (node (ref "TP4") (pin "TP") (pinfunction "TP_TP") (pintype "input"))
      (node (ref "U2") (pin "12") (pinfunction "VM_12") (pintype "bidirectional"))
      (node (ref "U3") (pin "12") (pinfunction "VM_12") (pintype "bidirectional"))
    )
    (net (code "8") (name "+VBAT_EPS") (class "Default")
      (node (ref "F1") (pin "1") (pinfunction "1_1") (pintype "bidirectional"))
      (node (ref "J2") (pin "97") (pinfunction "H2_45_97") (pintype "bidirectional"))
      (node (ref "J2") (pin "98") (pinfunction "H2_46_98") (pintype "bidirectional"))
    )
    (net (code "9") (name "GND") (class "Default")
      (node (ref "C1") (pin "2") (pinfunction "2_2") (pintype "passive"))
      (node (ref "C10") (pin "2") (pinfunction "2_2") (pintype "passive"))
      (node (ref "C13") (pin "2") (pinfunction "2_2") (pintype "passive"))
      (node (ref "C14") (pin "2") (pinfunction "2_2") (pintype "passive"))
      (node (ref "C15") (pin "2") (pinfunction "2_2") (pintype "passive"))
      (node (ref "C16") (pin "2") (pinfunction "2_2") (pintype "passive"))
      (node (ref "C17") (pin "2") (pinfunction "2_2") (pintype "passive"))
      (node (ref "C18") (pin "2") (pinfunction "2_2") (pintype "passive"))
      (node (ref "C19") (pin "2") (pinfunction "2_2") (pintype "passive"))
      (node (ref "C2") (pin "2") (pinfunction "2_2") (pintype "passive"))
      (node (ref "C20") (pin "-") (pinfunction "-_-") (pintype "passive"))
      (node (ref "C22") (pin "2") (pinfunction "2_2") (pintype "passive"))
      (node (ref "C23") (pin "-") (pinfunction "-_-") (pintype "passive"))
      (node (ref "C25") (pin "2") (pinfunction "2_2") (pintype "passive"))
      (node (ref "C26") (pin "2") (pinfunction "2_2") (pintype "passive"))
      (node (ref "C27") (pin "2") (pinfunction "2_2") (pintype "passive"))
      (node (ref "C28") (pin "1") (pinfunction "1_1") (pintype "passive"))
      (node (ref "C29") (pin "2") (pinfunction "2_2") (pintype "passive"))
      (node (ref "C3") (pin "2") (pinfunction "2_2") (pintype "passive"))
      (node (ref "C30") (pin "2") (pinfunction "2_2") (pintype "passive"))
      (node (ref "C32") (pin "2") (pinfunction "2_2") (pintype "passive"))
      (node (ref "C33") (pin "2") (pinfunction "2_2") (pintype "passive"))
      (node (ref "C34") (pin "2") (pinfunction "2_2") (pintype "passive"))
      (node (ref "C35") (pin "2") (pinfunction "2_2") (pintype "passive"))
      (node (ref "C37") (pin "2") (pinfunction "2_2") (pintype "passive"))
      (node (ref "C38") (pin "1") (pinfunction "1_1") (pintype "passive"))
      (node (ref "C39") (pin "2") (pinfunction "2_2") (pintype "passive"))
      (node (ref "C4") (pin "2") (pinfunction "2_2") (pintype "passive"))
      (node (ref "C40") (pin "1") (pinfunction "1_1") (pintype "passive"))
      (node (ref "C5") (pin "2") (pinfunction "2_2") (pintype "passive"))
      (node (ref "C6") (pin "2") (pinfunction "2_2") (pintype "passive"))
      (node (ref "C7") (pin "2") (pinfunction "2_2") (pintype "passive"))
      (node (ref "C8") (pin "2") (pinfunction "2_2") (pintype "passive"))
      (node (ref "C9") (pin "2") (pinfunction "2_2") (pintype "passive"))
      (node (ref "D1") (pin "1") (pinfunction "1_1") (pintype "bidirectional"))
      (node (ref "D2") (pin "1") (pinfunction "1_1") (pintype "bidirectional"))
      (node (ref "D3") (pin "1") (pinfunction "1_1") (pintype "bidirectional"))
      (node (ref "D4") (pin "1") (pinfunction "1_1") (pintype "bidirectional"))
      (node (ref "D5") (pin "1") (pinfunction "1_1") (pintype "bidirectional"))
      (node (ref "D6") (pin "1") (pinfunction "1_1") (pintype "bidirectional"))
      (node (ref "D7") (pin "1") (pinfunction "1_1") (pintype "bidirectional"))
      (node (ref "D8") (pin "1") (pinfunction "1_1") (pintype "bidirectional"))
      (node (ref "D9") (pin "1") (pinfunction "1_1") (pintype "bidirectional"))
      (node (ref "J1") (pin "3") (pinfunction "3_3") (pintype "bidirectional"))
      (node (ref "J1") (pin "5") (pinfunction "5_5") (pintype "bidirectional"))
      (node (ref "J1") (pin "9") (pinfunction "9_9") (pintype "bidirectional"))
      (node (ref "J2") (pin "81") (pinfunction "H2_29_81") (pintype "bidirectional"))
      (node (ref "J2") (pin "82") (pinfunction "H2_30_82") (pintype "bidirectional"))
      (node (ref "J2") (pin "83") (pinfunction "H2_31_83") (pintype "bidirectional"))
      (node (ref "J2") (pin "84") (pinfunction "H2_32_84") (pintype "bidirectional"))
      (node (ref "J3") (pin "2") (pinfunction "2_2") (pintype "passive"))
      (node (ref "J4") (pin "2") (pinfunction "2_2") (pintype "passive"))
      (node (ref "J5") (pin "2") (pinfunction "2_2") (pintype "passive"))
      (node (ref "J6") (pin "2") (pinfunction "2_2") (pintype "passive"))
      (node (ref "J7") (pin "5") (pinfunction "5_5") (pintype "passive"))
      (node (ref "J7") (pin "S1") (pinfunction "SHIELD_S1") (pintype "passive"))
      (node (ref "J7") (pin "S2") (pinfunction "SHIELD_S2") (pintype "passive"))
      (node (ref "J7") (pin "S3") (pinfunction "SHIELD_S3") (pintype "passive"))
      (node (ref "J7") (pin "S4") (pinfunction "SHIELD_S4") (pintype "passive"))
      (node (ref "J7") (pin "S5") (pinfunction "SHIELD_S5") (pintype "passive"))
      (node (ref "J7") (pin "S6") (pinfunction "SHIELD_S6") (pintype "passive"))
      (node (ref "J8") (pin "3") (pinfunction "GND_3") (pintype "passive"))
      (node (ref "J8") (pin "6") (pinfunction "GND_6") (pintype "passive"))
      (node (ref "J8") (pin "9") (pinfunction "GND_9") (pintype "passive"))
      (node (ref "J9") (pin "6") (pinfunction "VSS_6") (pintype "power_in"))
      (node (ref "J9") (pin "9") (pinfunction "DETECH_9") (pintype "passive"))
      (node (ref "LED1") (pin "C") (pinfunction "C_C") (pintype "passive"))
      (node (ref "LED2") (pin "C") (pinfunction "C_C") (pintype "passive"))
      (node (ref "LED3") (pin "C") (pinfunction "C_C") (pintype "passive"))
      (node (ref "LED4") (pin "C") (pinfunction "C_C") (pintype "passive"))
      (node (ref "LED5") (pin "C") (pinfunction "C_C") (pintype "passive"))
      (node (ref "R27") (pin "2") (pinfunction "2_2") (pintype "passive"))
      (node (ref "R3") (pin "1") (pinfunction "1_1") (pintype "passive"))
      (node (ref "R4") (pin "1") (pinfunction "1_1") (pintype "passive"))
      (node (ref "R5") (pin "1") (pinfunction "1_1") (pintype "passive"))
      (node (ref "R6") (pin "1") (pinfunction "1_1") (pintype "passive"))
      (node (ref "R9") (pin "1") (pinfunction "1_1") (pintype "passive"))
      (node (ref "S1") (pin "3") (pinfunction "P_3") (pintype "passive"))
      (node (ref "S1") (pin "4") (pinfunction "P1_4") (pintype "passive"))
      (node (ref "TP15") (pin "TP") (pinfunction "TP_TP") (pintype "input"))
      (node (ref "TP16") (pin "TP") (pinfunction "TP_TP") (pintype "input"))
      (node (ref "TP19") (pin "TP") (pinfunction "TP_TP") (pintype "input"))
      (node (ref "TP20") (pin "TP") (pinfunction "TP_TP") (pintype "input"))
      (node (ref "U1") (pin "12") (pinfunction "GND_2_12") (pintype "power_in"))
      (node (ref "U1") (pin "27") (pinfunction "GND_3_27") (pintype "power_in"))
      (node (ref "U1") (pin "3") (pinfunction "GNDA_3") (pintype "power_in"))
      (node (ref "U1") (pin "39") (pinfunction "GND_4_39") (pintype "power_in"))
      (node (ref "U1") (pin "55") (pinfunction "GND_55") (pintype "power_in"))
      (node (ref "U12") (pin "4") (pinfunction "GND_4") (pintype "bidirectional"))
      (node (ref "U12") (pin "9") (pinfunction "PAD_9") (pintype "bidirectional"))
      (node (ref "U2") (pin "13") (pinfunction "GND_13") (pintype "power_in"))
      (node (ref "U3") (pin "13") (pinfunction "GND_13") (pintype "power_in"))
      (node (ref "U4") (pin "2") (pinfunction "GND_2") (pintype "power_in"))
      (node (ref "U5") (pin "2") (pinfunction "GND_2") (pintype "power_in"))
      (node (ref "U6") (pin "2") (pinfunction "GND_2") (pintype "power_in"))
    )
    (net (code "10") (name "GNDX") (class "Default")
      (node (ref "C11") (pin "2") (pinfunction "2_2") (pintype "passive"))
      (node (ref "C12") (pin "1") (pinfunction "1_1") (pintype "passive"))
      (node (ref "U1") (pin "35") (pinfunction "GNDX_35") (pintype "power_in"))
    )
    (net (code "11") (name "M0_CHA") (class "Default")
      (node (ref "J4") (pin "3") (pinfunction "3_3") (pintype "passive"))
      (node (ref "U1") (pin "47") (pinfunction "PB2_I2C0SCL_47") (pintype "bidirectional"))
    )
    (net (code "12") (name "M0_CHB") (class "Default")
      (node (ref "J4") (pin "4") (pinfunction "4_4") (pintype "passive"))
      (node (ref "U1") (pin "48") (pinfunction "PB3_I2C0SDA_48") (pintype "bidirectional"))
    )
    (net (code "13") (name "M0_IN1") (class "Default")
      (node (ref "TP7") (pin "TP") (pinfunction "TP_TP") (pintype "input"))
      (node (ref "U1") (pin "15") (pinfunction "PC5_15") (pintype "bidirectional"))
      (node (ref "U2") (pin "16") (pinfunction "A_IN1_16") (pintype "input"))
    )
    (net (code "14") (name "M0_IN2") (class "Default")
      (node (ref "TP8") (pin "TP") (pinfunction "TP_TP") (pintype "input"))
      (node (ref "U1") (pin "16") (pinfunction "PC4_16") (pintype "bidirectional"))
      (node (ref "U2") (pin "15") (pinfunction "A_IN2_15") (pintype "input"))
    )
    (net (code "15") (name "M0_OUT1") (class "Default")
      (node (ref "J4") (pin "1") (pinfunction "1_1") (pintype "passive"))
      (node (ref "U2") (pin "2") (pinfunction "A_OUT1_2") (pintype "output"))
    )
    (net (code "16") (name "M0_OUT2") (class "Default")
      (node (ref "J4") (pin "6") (pinfunction "6_6") (pintype "passive"))
      (node (ref "U2") (pin "4") (pinfunction "A_OUT2_4") (pintype "output"))
    )
    (net (code "17") (name "M1_CHA") (class "Default")
      (node (ref "J3") (pin "3") (pinfunction "3_3") (pintype "passive"))
      (node (ref "U1") (pin "58") (pinfunction "PB4_58") (pintype "bidirectional"))
    )
    (net (code "18") (name "M1_CHB") (class "Default")
      (node (ref "J3") (pin "4") (pinfunction "4_4") (pintype "passive"))
      (node (ref "U1") (pin "57") (pinfunction "PB5_57") (pintype "bidirectional"))
    )
    (net (code "19") (name "M1_IN1") (class "Default")
      (node (ref "TP9") (pin "TP") (pinfunction "TP_TP") (pintype "input"))
      (node (ref "U1") (pin "13") (pinfunction "PC7_13") (pintype "bidirectional"))
      (node (ref "U2") (pin "9") (pinfunction "B_IN1_9") (pintype "input"))
    )
    (net (code "20") (name "M1_IN2") (class "Default")
      (node (ref "TP10") (pin "TP") (pinfunction "TP_TP") (pintype "input"))
      (node (ref "U1") (pin "14") (pinfunction "PC6_14") (pintype "bidirectional"))
      (node (ref "U2") (pin "10") (pinfunction "B_IN2_10") (pintype "input"))
    )
    (net (code "21") (name "M1_OUT1") (class "Default")
      (node (ref "J3") (pin "1") (pinfunction "1_1") (pintype "passive"))
      (node (ref "U2") (pin "7") (pinfunction "B_OUT1_7") (pintype "output"))
    )
    (net (code "22") (name "M1_OUT2") (class "Default")
      (node (ref "J3") (pin "6") (pinfunction "6_6") (pintype "passive"))
      (node (ref "U2") (pin "5") (pinfunction "B_OUT2_5") (pintype "output"))
    )
    (net (code "23") (name "M01_SLEEP") (class "Default")
      (node (ref "U1") (pin "7") (pinfunction "PE2_7") (pintype "bidirectional"))
      (node (ref "U2") (pin "1") (pinfunction "NSLEEP_1") (pintype "bidirectional"))
    )
    (net (code "24") (name "M2_CHA") (class "Default")
      (node (ref "J5") (pin "3") (pinfunction "3_3") (pintype "passive"))
      (node (ref "U1") (pin "1") (pinfunction "PB6_1") (pintype "bidirectional"))
    )
    (net (code "25") (name "M2_CHB") (class "Default")
      (node (ref "J5") (pin "4") (pinfunction "4_4") (pintype "passive"))
      (node (ref "U1") (pin "4") (pinfunction "PB7_4") (pintype "bidirectional"))
    )
    (net (code "26") (name "M2_IN1") (class "Default")
      (node (ref "TP11") (pin "TP") (pinfunction "TP_TP") (pintype "input"))
      (node (ref "U1") (pin "64") (pinfunction "PD3_64") (pintype "bidirectional"))
      (node (ref "U3") (pin "16") (pinfunction "A_IN1_16") (pintype "input"))
    )
    (net (code "27") (name "M2_IN2") (class "Default")
      (node (ref "TP12") (pin "TP") (pinfunction "TP_TP") (pintype "input"))
      (node (ref "U1") (pin "63") (pinfunction "PD2_63") (pintype "bidirectional"))
      (node (ref "U3") (pin "15") (pinfunction "A_IN2_15") (pintype "input"))
    )
    (net (code "28") (name "M2_OUT1") (class "Default")
      (node (ref "J5") (pin "1") (pinfunction "1_1") (pintype "passive"))
      (node (ref "U3") (pin "2") (pinfunction "A_OUT1_2") (pintype "output"))
    )
    (net (code "29") (name "M2_OUT2") (class "Default")
      (node (ref "J5") (pin "6") (pinfunction "6_6") (pintype "passive"))
      (node (ref "U3") (pin "4") (pinfunction "A_OUT2_4") (pintype "output"))
    )
    (net (code "30") (name "M3_CHA") (class "Default")
      (node (ref "J6") (pin "3") (pinfunction "3_3") (pintype "passive"))
      (node (ref "U1") (pin "9") (pinfunction "PE0_9") (pintype "bidirectional"))
    )
    (net (code "31") (name "M3_CHB") (class "Default")
      (node (ref "J6") (pin "4") (pinfunction "4_4") (pintype "passive"))
      (node (ref "U1") (pin "8") (pinfunction "PE1_8") (pintype "bidirectional"))
    )
    (net (code "32") (name "M3_IN1") (class "Default")
      (node (ref "TP13") (pin "TP") (pinfunction "TP_TP") (pintype "input"))
      (node (ref "U1") (pin "62") (pinfunction "PD1_62") (pintype "bidirectional"))
      (node (ref "U3") (pin "9") (pinfunction "B_IN1_9") (pintype "input"))
    )
    (net (code "33") (name "M3_IN2") (class "Default")
      (node (ref "TP14") (pin "TP") (pinfunction "TP_TP") (pintype "input"))
      (node (ref "U1") (pin "61") (pinfunction "PD0_61") (pintype "bidirectional"))
      (node (ref "U3") (pin "10") (pinfunction "B_IN2_10") (pintype "input"))
    )
    (net (code "34") (name "M3_OUT1") (class "Default")
      (node (ref "J6") (pin "1") (pinfunction "1_1") (pintype "passive"))
      (node (ref "U3") (pin "7") (pinfunction "B_OUT1_7") (pintype "output"))
    )
    (net (code "35") (name "M3_OUT2") (class "Default")
      (node (ref "J6") (pin "6") (pinfunction "6_6") (pintype "passive"))
      (node (ref "U3") (pin "5") (pinfunction "B_OUT2_5") (pintype "output"))
    )
    (net (code "36") (name "M23_SLEEP") (class "Default")
      (node (ref "U1") (pin "6") (pinfunction "PE3_6") (pintype "bidirectional"))
      (node (ref "U3") (pin "1") (pinfunction "NSLEEP_1") (pintype "bidirectional"))
    )
    (net (code "37") (name "Net-(C36-Pad2)") (class "Default")
      (node (ref "C36") (pin "2") (pinfunction "2_2") (pintype "passive"))
      (node (ref "R27") (pin "1") (pinfunction "1_1") (pintype "passive"))
    )
    (net (code "38") (name "Net-(F2-Pad2)") (class "Default")
      (node (ref "F2") (pin "2") (pinfunction "2_2") (pintype "passive"))
      (node (ref "J7") (pin "1") (pinfunction "1_1") (pintype "passive"))
    )
    (net (code "39") (name "Net-(J8-PPM)") (class "Default")
      (node (ref "D1") (pin "2") (pinfunction "2_2") (pintype "bidirectional"))
      (node (ref "J8") (pin "1") (pinfunction "PPM_1") (pintype "passive"))
      (node (ref "R12") (pin "1") (pinfunction "1_1") (pintype "passive"))
    )
    (net (code "40") (name "Net-(J8-SERVO_0)") (class "Default")
      (node (ref "D2") (pin "2") (pinfunction "2_2") (pintype "bidirectional"))
      (node (ref "J8") (pin "4") (pinfunction "SERVO_0_4") (pintype "passive"))
      (node (ref "R25") (pin "1") (pinfunction "1_1") (pintype "passive"))
    )
    (net (code "41") (name "Net-(J8-SERVO_1)") (class "Default")
      (node (ref "D3") (pin "2") (pinfunction "2_2") (pintype "bidirectional"))
      (node (ref "J8") (pin "7") (pinfunction "SERVO_1_7") (pintype "passive"))
      (node (ref "R26") (pin "1") (pinfunction "1_1") (pintype "passive"))
    )
    (net (code "42") (name "Net-(J9-DATA1)") (class "Default")
      (node (ref "J9") (pin "8") (pinfunction "DATA1_8") (pintype "bidirectional"))
      (node (ref "R17") (pin "1") (pinfunction "1_1") (pintype "passive"))
    )
    (net (code "43") (name "Net-(J9-DATA2)") (class "Default")
      (node (ref "J9") (pin "1") (pinfunction "DATA2_1") (pintype "bidirectional"))
      (node (ref "R16") (pin "1") (pinfunction "1_1") (pintype "passive"))
    )
    (net (code "44") (name "Net-(LED1-PadA)") (class "Default")
      (node (ref "LED1") (pin "A") (pinfunction "A_A") (pintype "passive"))
      (node (ref "R13") (pin "2") (pinfunction "2_2") (pintype "passive"))
    )
    (net (code "45") (name "Net-(LED2-PadA)") (class "Default")
      (node (ref "LED2") (pin "A") (pinfunction "A_A") (pintype "passive"))
      (node (ref "R20") (pin "1") (pinfunction "1_1") (pintype "passive"))
    )
    (net (code "46") (name "Net-(LED3-PadA)") (class "Default")
      (node (ref "LED3") (pin "A") (pinfunction "A_A") (pintype "passive"))
      (node (ref "R21") (pin "1") (pinfunction "1_1") (pintype "passive"))
    )
    (net (code "47") (name "Net-(LED4-PadA)") (class "Default")
      (node (ref "LED4") (pin "A") (pinfunction "A_A") (pintype "passive"))
      (node (ref "R22") (pin "1") (pinfunction "1_1") (pintype "passive"))
    )
    (net (code "48") (name "Net-(LED5-PadA)") (class "Default")
      (node (ref "LED5") (pin "A") (pinfunction "A_A") (pintype "passive"))
      (node (ref "R11") (pin "2") (pinfunction "2_2") (pintype "passive"))
    )
    (net (code "49") (name "Net-(U1-OSC0)") (class "Default")
      (node (ref "C14") (pin "1") (pinfunction "1_1") (pintype "passive"))
      (node (ref "U1") (pin "40") (pinfunction "OSC0_40") (pintype "input"))
      (node (ref "Y1") (pin "1") (pinfunction "1_1") (pintype "bidirectional"))
    )
    (net (code "50") (name "Net-(U1-OSC1)") (class "Default")
      (node (ref "C15") (pin "1") (pinfunction "1_1") (pintype "passive"))
      (node (ref "U1") (pin "41") (pinfunction "OSC1_41") (pintype "output"))
      (node (ref "Y1") (pin "3") (pinfunction "2_3") (pintype "bidirectional"))
    )
    (net (code "51") (name "Net-(U1-PF0)") (class "Default")
      (node (ref "R20") (pin "2") (pinfunction "2_2") (pintype "passive"))
      (node (ref "U1") (pin "28") (pinfunction "PF0_28") (pintype "bidirectional"))
    )
    (net (code "52") (name "Net-(U1-PF1)") (class "Default")
      (node (ref "R21") (pin "2") (pinfunction "2_2") (pintype "passive"))
      (node (ref "U1") (pin "29") (pinfunction "PF1_29") (pintype "bidirectional"))
    )
    (net (code "53") (name "Net-(U1-PF2)") (class "Default")
      (node (ref "R22") (pin "2") (pinfunction "2_2") (pintype "passive"))
      (node (ref "U1") (pin "30") (pinfunction "PF2_30") (pintype "bidirectional"))
    )
    (net (code "54") (name "Net-(U1-VDDC)") (class "Default")
      (node (ref "C10") (pin "1") (pinfunction "1_1") (pintype "passive"))
      (node (ref "C7") (pin "1") (pinfunction "1_1") (pintype "passive"))
      (node (ref "C8") (pin "1") (pinfunction "1_1") (pintype "passive"))
      (node (ref "C9") (pin "1") (pinfunction "1_1") (pintype "passive"))
      (node (ref "U1") (pin "25") (pinfunction "VDDC_2_25") (pintype "power_in"))
      (node (ref "U1") (pin "56") (pinfunction "VDDC_56") (pintype "power_in"))
    )
    (net (code "55") (name "Net-(U1-WAKE_N)") (class "Default")
      (node (ref "R1") (pin "2") (pinfunction "2_2") (pintype "passive"))
      (node (ref "TP18") (pin "TP") (pinfunction "TP_TP") (pintype "input"))
      (node (ref "U1") (pin "32") (pinfunction "WAKE_N_32") (pintype "input"))
    )
    (net (code "56") (name "Net-(U1-XOSC0)") (class "Default")
      (node (ref "C12") (pin "2") (pinfunction "2_2") (pintype "passive"))
      (node (ref "U1") (pin "34") (pinfunction "XOSC0_34") (pintype "input"))
      (node (ref "Y2") (pin "2") (pinfunction "2_2") (pintype "bidirectional"))
    )
    (net (code "57") (name "Net-(U1-XOSC1)") (class "Default")
      (node (ref "C11") (pin "1") (pinfunction "1_1") (pintype "passive"))
      (node (ref "U1") (pin "36") (pinfunction "XOSC1_36") (pintype "output"))
      (node (ref "Y2") (pin "1") (pinfunction "1_1") (pintype "bidirectional"))
    )
    (net (code "58") (name "Net-(U2-A_ISENSE)") (class "Default")
      (node (ref "R3") (pin "2") (pinfunction "2_2") (pintype "passive"))
      (node (ref "U2") (pin "3") (pinfunction "A_ISENSE_3") (pintype "bidirectional"))
    )
    (net (code "59") (name "Net-(U2-B_ISENSE)") (class "Default")
      (node (ref "R4") (pin "2") (pinfunction "2_2") (pintype "passive"))
      (node (ref "U2") (pin "6") (pinfunction "B_ISENSE_6") (pintype "bidirectional"))
    )
    (net (code "60") (name "Net-(U2-NFAULT)") (class "Default")
      (node (ref "TP22") (pin "TP") (pinfunction "TP_TP") (pintype "input"))
      (node (ref "U2") (pin "8") (pinfunction "NFAULT_8") (pintype "bidirectional"))
    )
    (net (code "61") (name "Net-(U2-VCP)") (class "Default")
      (node (ref "C21") (pin "2") (pinfunction "2_2") (pintype "passive"))
      (node (ref "U2") (pin "11") (pinfunction "VCP_11") (pintype "bidirectional"))
    )
    (net (code "62") (name "Net-(U2-VINT)") (class "Default")
      (node (ref "C22") (pin "1") (pinfunction "1_1") (pintype "passive"))
      (node (ref "U2") (pin "14") (pinfunction "VINT_14") (pintype "input"))
    )
    (net (code "63") (name "Net-(U3-A_ISENSE)") (class "Default")
      (node (ref "R5") (pin "2") (pinfunction "2_2") (pintype "passive"))
      (node (ref "U3") (pin "3") (pinfunction "A_ISENSE_3") (pintype "bidirectional"))
    )
    (net (code "64") (name "Net-(U3-B_ISENSE)") (class "Default")
      (node (ref "R6") (pin "2") (pinfunction "2_2") (pintype "passive"))
      (node (ref "U3") (pin "6") (pinfunction "B_ISENSE_6") (pintype "bidirectional"))
    )
    (net (code "65") (name "Net-(U3-NFAULT)") (class "Default")
      (node (ref "TP21") (pin "TP") (pinfunction "TP_TP") (pintype "input"))
      (node (ref "U3") (pin "8") (pinfunction "NFAULT_8") (pintype "bidirectional"))
    )
    (net (code "66") (name "Net-(U3-VCP)") (class "Default")
      (node (ref "C24") (pin "2") (pinfunction "2_2") (pintype "passive"))
      (node (ref "U3") (pin "11") (pinfunction "VCP_11") (pintype "bidirectional"))
    )
    (net (code "67") (name "Net-(U3-VINT)") (class "Default")
      (node (ref "C25") (pin "1") (pinfunction "1_1") (pintype "passive"))
      (node (ref "U3") (pin "14") (pinfunction "VINT_14") (pintype "input"))
    )
    (net (code "68") (name "Net-(U4-NR)") (class "Default")
      (node (ref "C27") (pin "1") (pinfunction "1_1") (pintype "passive"))
      (node (ref "U4") (pin "4") (pinfunction "NR_4") (pintype "passive"))
    )
    (net (code "69") (name "Net-(U5-OE)") (class "Default")
      (node (ref "R7") (pin "1") (pinfunction "1_1") (pintype "passive"))
      (node (ref "U5") (pin "6") (pinfunction "OE_6") (pintype "input"))
    )
    (net (code "70") (name "Net-(U6-OE)") (class "Default")
      (node (ref "R10") (pin "1") (pinfunction "1_1") (pintype "passive"))
      (node (ref "U6") (pin "6") (pinfunction "OE_6") (pintype "input"))
    )
    (net (code "71") (name "Net-(U12-BOOT)") (class "Default")
      (node (ref "C31") (pin "1") (pinfunction "1_1") (pintype "passive"))
      (node (ref "U12") (pin "1") (pinfunction "BOOT_1") (pintype "bidirectional"))
    )
    (net (code "72") (name "Net-(U12-COMP)") (class "Default")
      (node (ref "C36") (pin "1") (pinfunction "1_1") (pintype "passive"))
      (node (ref "C37") (pin "1") (pinfunction "1_1") (pintype "passive"))
      (node (ref "U12") (pin "6") (pinfunction "COMP_6") (pintype "bidirectional"))
    )
    (net (code "73") (name "Net-(U12-FB)") (class "Default")
      (node (ref "R8") (pin "1") (pinfunction "1_1") (pintype "passive"))
      (node (ref "R9") (pin "2") (pinfunction "2_2") (pintype "passive"))
      (node (ref "TP3") (pin "TP") (pinfunction "TP_TP") (pintype "input"))
      (node (ref "U12") (pin "5") (pinfunction "FB_5") (pintype "bidirectional"))
    )
    (net (code "74") (name "Net-(U12-SS)") (class "Default")
      (node (ref "C29") (pin "1") (pinfunction "1_1") (pintype "passive"))
      (node (ref "U12") (pin "8") (pinfunction "SS_8") (pintype "bidirectional"))
    )
    (net (code "75") (name "Net-(U12-SW)") (class "Default")
      (node (ref "C31") (pin "2") (pinfunction "2_2") (pintype "passive"))
      (node (ref "L1") (pin "1") (pinfunction "1_1") (pintype "bidirectional"))
      (node (ref "U12") (pin "3") (pinfunction "SW_3") (pintype "bidirectional"))
    )
    (net (code "76") (name "Net-(U12-VIN)") (class "Default")
      (node (ref "C17") (pin "1") (pinfunction "1_1") (pintype "passive"))
      (node (ref "C18") (pin "1") (pinfunction "1_1") (pintype "passive"))
      (node (ref "F1") (pin "2") (pinfunction "2_2") (pintype "bidirectional"))
      (node (ref "R23") (pin "1") (pinfunction "1_1") (pintype "passive"))
      (node (ref "TP5") (pin "TP") (pinfunction "TP_TP") (pintype "input"))
      (node (ref "U12") (pin "2") (pinfunction "VIN_2") (pintype "bidirectional"))
    )
    (net (code "77") (name "OBC_CAN+") (class "Default")
      (node (ref "J2") (pin "1") (pinfunction "H1_1_1") (pintype "bidirectional"))
      (node (ref "U1") (pin "59") (pinfunction "PE4_59") (pintype "bidirectional"))
    )
    (net (code "78") (name "OBC_CAN-") (class "Default")
      (node (ref "J2") (pin "3") (pinfunction "H1_3_3") (pintype "bidirectional"))
      (node (ref "U1") (pin "60") (pinfunction "PE5_60") (pintype "bidirectional"))
    )
    (net (code "79") (name "OBC_RX") (class "Default")
      (node (ref "J2") (pin "40") (pinfunction "H1_40_40") (pintype "bidirectional"))
      (node (ref "U1") (pin "17") (pinfunction "PA0_U0RX_17") (pintype "bidirectional"))
    )
    (net (code "80") (name "OBC_SCL") (class "Default")
      (node (ref "J2") (pin "21") (pinfunction "H1_21_21") (pintype "bidirectional"))
      (node (ref "R24") (pin "1") (pinfunction "1_1") (pintype "passive"))
      (node (ref "U1") (pin "23") (pinfunction "PA6_23") (pintype "bidirectional"))
    )
    (net (code "81") (name "OBC_SDA") (class "Default")
      (node (ref "J2") (pin "23") (pinfunction "H1_23_23") (pintype "bidirectional"))
      (node (ref "R19") (pin "1") (pinfunction "1_1") (pintype "passive"))
      (node (ref "U1") (pin "24") (pinfunction "PA7_24") (pintype "bidirectional"))
    )
    (net (code "82") (name "OBC_TX") (class "Default")
      (node (ref "J2") (pin "39") (pinfunction "H1_39_39") (pintype "bidirectional"))
      (node (ref "U1") (pin "18") (pinfunction "PA1_U0TX_18") (pintype "bidirectional"))
    )
    (net (code "83") (name "PPM") (class "Default")
      (node (ref "U1") (pin "53") (pinfunction "PD6_53") (pintype "bidirectional"))
      (node (ref "U6") (pin "5") (pinfunction "A1_5") (pintype "bidirectional"))
    )
    (net (code "84") (name "PPM_IN") (class "Default")
      (node (ref "R12") (pin "2") (pinfunction "2_2") (pintype "passive"))
      (node (ref "U6") (pin "8") (pinfunction "B1_8") (pintype "bidirectional"))
    )
    (net (code "85") (name "SD_MISO") (class "Default")
      (node (ref "D6") (pin "2") (pinfunction "2_2") (pintype "bidirectional"))
      (node (ref "J9") (pin "7") (pinfunction "DATA0_7") (pintype "bidirectional"))
      (node (ref "R18") (pin "1") (pinfunction "1_1") (pintype "passive"))
      (node (ref "U1") (pin "21") (pinfunction "PA4_SSI0RX_21") (pintype "bidirectional"))
    )
    (net (code "86") (name "SD_MOSI") (class "Default")
      (node (ref "D4") (pin "2") (pinfunction "2_2") (pintype "bidirectional"))
      (node (ref "J9") (pin "3") (pinfunction "CMD_3") (pintype "bidirectional"))
      (node (ref "R14") (pin "1") (pinfunction "1_1") (pintype "passive"))
      (node (ref "U1") (pin "22") (pinfunction "PA5_SSI0TX_22") (pintype "bidirectional"))
    )
    (net (code "87") (name "SD_SCK") (class "Default")
      (node (ref "D7") (pin "2") (pinfunction "2_2") (pintype "bidirectional"))
      (node (ref "J9") (pin "5") (pinfunction "CLK_5") (pintype "bidirectional"))
      (node (ref "U1") (pin "19") (pinfunction "PA2_SSI0CLK_19") (pintype "bidirectional"))
    )
    (net (code "88") (name "SERVO_0") (class "Default")
      (node (ref "U1") (pin "45") (pinfunction "PB0_45") (pintype "bidirectional"))
      (node (ref "U5") (pin "5") (pinfunction "A1_5") (pintype "bidirectional"))
    )
    (net (code "89") (name "SERVO_0_OUT") (class "Default")
      (node (ref "R25") (pin "2") (pinfunction "2_2") (pintype "passive"))
      (node (ref "U5") (pin "8") (pinfunction "B1_8") (pintype "bidirectional"))
    )
    (net (code "90") (name "SERVO_1") (class "Default")
      (node (ref "U1") (pin "46") (pinfunction "PB1_46") (pintype "bidirectional"))
      (node (ref "U5") (pin "4") (pinfunction "A2_4") (pintype "bidirectional"))
    )
    (net (code "91") (name "SERVO_1_OUT") (class "Default")
      (node (ref "R26") (pin "2") (pinfunction "2_2") (pintype "passive"))
      (node (ref "U5") (pin "1") (pinfunction "B2_1") (pintype "bidirectional"))
    )
    (net (code "92") (name "TCK") (class "Default")
      (node (ref "J1") (pin "4") (pinfunction "4_4") (pintype "bidirectional"))
      (node (ref "U1") (pin "52") (pinfunction "PC0_TCK_SWCLK_52") (pintype "bidirectional"))
    )
    (net (code "93") (name "TDI") (class "Default")
      (node (ref "J1") (pin "8") (pinfunction "8_8") (pintype "bidirectional"))
      (node (ref "U1") (pin "50") (pinfunction "PC2_TDI_50") (pintype "bidirectional"))
    )
    (net (code "94") (name "TDO") (class "Default")
      (node (ref "J1") (pin "6") (pinfunction "6_6") (pintype "bidirectional"))
      (node (ref "U1") (pin "49") (pinfunction "PC3_TDO_SWO_49") (pintype "bidirectional"))
    )
    (net (code "95") (name "TMS") (class "Default")
      (node (ref "J1") (pin "2") (pinfunction "2_2") (pintype "bidirectional"))
      (node (ref "U1") (pin "51") (pinfunction "PC1_TMS_SWDIO_51") (pintype "bidirectional"))
    )
    (net (code "96") (name "USB_D+") (class "Default")
      (node (ref "D9") (pin "2") (pinfunction "2_2") (pintype "bidirectional"))
      (node (ref "J7") (pin "3") (pinfunction "3_3") (pintype "passive"))
      (node (ref "U1") (pin "44") (pinfunction "PD5_44") (pintype "bidirectional"))
    )
    (net (code "97") (name "USB_D-") (class "Default")
      (node (ref "D8") (pin "2") (pinfunction "2_2") (pintype "bidirectional"))
      (node (ref "J7") (pin "2") (pinfunction "2_2") (pintype "passive"))
      (node (ref "U1") (pin "43") (pinfunction "PD4_43") (pintype "bidirectional"))
    )
    (net (code "98") (name "USB_ID") (class "Default")
      (node (ref "J7") (pin "4") (pinfunction "4_4") (pintype "passive"))
    )
    (net (code "99") (name "VMOT_EN") (class "Default")
      (node (ref "C40") (pin "2") (pinfunction "2_2") (pintype "passive"))
      (node (ref "R23") (pin "2") (pinfunction "2_2") (pintype "passive"))
      (node (ref "U1") (pin "31") (pinfunction "PF3_31") (pintype "bidirectional"))
      (node (ref "U12") (pin "7") (pinfunction "EN_7") (pintype "bidirectional"))
    )
    (net (code "100") (name "unconnected-(J1-Pad7)") (class "Default")
      (node (ref "J1") (pin "7") (pinfunction "7_7") (pintype "bidirectional"))
    )
    (net (code "101") (name "unconnected-(J2-H1_2-Pad2)") (class "Default")
      (node (ref "J2") (pin "2") (pinfunction "H1_2_2") (pintype "bidirectional"))
    )
    (net (code "102") (name "unconnected-(J2-H1_4-Pad4)") (class "Default")
      (node (ref "J2") (pin "4") (pinfunction "H1_4_4") (pintype "bidirectional"))
    )
    (net (code "103") (name "unconnected-(J2-H1_5-Pad5)") (class "Default")
      (node (ref "J2") (pin "5") (pinfunction "H1_5_5") (pintype "bidirectional"))
    )
    (net (code "104") (name "unconnected-(J2-H1_6-Pad6)") (class "Default")
      (node (ref "J2") (pin "6") (pinfunction "H1_6_6") (pintype "bidirectional"))
    )
    (net (code "105") (name "unconnected-(J2-H1_7-Pad7)") (class "Default")
      (node (ref "J2") (pin "7") (pinfunction "H1_7_7") (pintype "bidirectional"))
    )
    (net (code "106") (name "unconnected-(J2-H1_8-Pad8)") (class "Default")
      (node (ref "J2") (pin "8") (pinfunction "H1_8_8") (pintype "bidirectional"))
    )
    (net (code "107") (name "unconnected-(J2-H1_9-Pad9)") (class "Default")
      (node (ref "J2") (pin "9") (pinfunction "H1_9_9") (pintype "bidirectional"))
    )
    (net (code "108") (name "unconnected-(J2-H1_10-Pad10)") (class "Default")
      (node (ref "J2") (pin "10") (pinfunction "H1_10_10") (pintype "bidirectional"))
    )
    (net (code "109") (name "unconnected-(J2-H1_11-Pad11)") (class "Default")
      (node (ref "J2") (pin "11") (pinfunction "H1_11_11") (pintype "bidirectional"))
    )
    (net (code "110") (name "unconnected-(J2-H1_12-Pad12)") (class "Default")
      (node (ref "J2") (pin "12") (pinfunction "H1_12_12") (pintype "bidirectional"))
    )
    (net (code "111") (name "unconnected-(J2-H1_13-Pad13)") (class "Default")
      (node (ref "J2") (pin "13") (pinfunction "H1_13_13") (pintype "bidirectional"))
    )
    (net (code "112") (name "unconnected-(J2-H1_14-Pad14)") (class "Default")
      (node (ref "J2") (pin "14") (pinfunction "H1_14_14") (pintype "bidirectional"))
    )
    (net (code "113") (name "unconnected-(J2-H1_15-Pad15)") (class "Default")
      (node (ref "J2") (pin "15") (pinfunction "H1_15_15") (pintype "bidirectional"))
    )
    (net (code "114") (name "unconnected-(J2-H1_16-Pad16)") (class "Default")
      (node (ref "J2") (pin "16") (pinfunction "H1_16_16") (pintype "bidirectional"))
    )
    (net (code "115") (name "unconnected-(J2-H1_17-Pad17)") (class "Default")
      (node (ref "J2") (pin "17") (pinfunction "H1_17_17") (pintype "bidirectional"))
    )
    (net (code "116") (name "unconnected-(J2-H1_18-Pad18)") (class "Default")
      (node (ref "J2") (pin "18") (pinfunction "H1_18_18") (pintype "bidirectional"))
    )
    (net (code "117") (name "unconnected-(J2-H1_19-Pad19)") (class "Default")
      (node (ref "J2") (pin "19") (pinfunction "H1_19_19") (pintype "bidirectional"))
    )
    (net (code "118") (name "unconnected-(J2-H1_20-Pad20)") (class "Default")
      (node (ref "J2") (pin "20") (pinfunction "H1_20_20") (pintype "bidirectional"))
    )
    (net (code "119") (name "unconnected-(J2-H1_22-Pad22)") (class "Default")
      (node (ref "J2") (pin "22") (pinfunction "H1_22_22") (pintype "bidirectional"))
    )
    (net (code "120") (name "unconnected-(J2-H1_24-Pad24)") (class "Default")
      (node (ref "J2") (pin "24") (pinfunction "H1_24_24") (pintype "bidirectional"))
    )
    (net (code "121") (name "unconnected-(J2-H1_25-Pad25)") (class "Default")
      (node (ref "J2") (pin "25") (pinfunction "H1_25_25") (pintype "bidirectional"))
    )
    (net (code "122") (name "unconnected-(J2-H1_26-Pad26)") (class "Default")
      (node (ref "J2") (pin "26") (pinfunction "H1_26_26") (pintype "bidirectional"))
    )
    (net (code "123") (name "unconnected-(J2-H1_27-Pad27)") (class "Default")
      (node (ref "J2") (pin "27") (pinfunction "H1_27_27") (pintype "bidirectional"))
    )
    (net (code "124") (name "unconnected-(J2-H1_28-Pad28)") (class "Default")
      (node (ref "J2") (pin "28") (pinfunction "H1_28_28") (pintype "bidirectional"))
    )
    (net (code "125") (name "unconnected-(J2-H1_29-Pad29)") (class "Default")
      (node (ref "J2") (pin "29") (pinfunction "H1_29_29") (pintype "bidirectional"))
    )
    (net (code "126") (name "unconnected-(J2-H1_30-Pad30)") (class "Default")
      (node (ref "J2") (pin "30") (pinfunction "H1_30_30") (pintype "bidirectional"))
    )
    (net (code "127") (name "unconnected-(J2-H1_31-Pad31)") (class "Default")
      (node (ref "J2") (pin "31") (pinfunction "H1_31_31") (pintype "bidirectional"))
    )
    (net (code "128") (name "unconnected-(J2-H1_32-Pad32)") (class "Default")
      (node (ref "J2") (pin "32") (pinfunction "H1_32_32") (pintype "bidirectional"))
    )
    (net (code "129") (name "unconnected-(J2-H1_33-Pad33)") (class "Default")
      (node (ref "J2") (pin "33") (pinfunction "H1_33_33") (pintype "bidirectional"))
    )
    (net (code "130") (name "unconnected-(J2-H1_34-Pad34)") (class "Default")
      (node (ref "J2") (pin "34") (pinfunction "H1_34_34") (pintype "bidirectional"))
    )
    (net (code "131") (name "unconnected-(J2-H1_35-Pad35)") (class "Default")
      (node (ref "J2") (pin "35") (pinfunction "H1_35_35") (pintype "bidirectional"))
    )
    (net (code "132") (name "unconnected-(J2-H1_36-Pad36)") (class "Default")
      (node (ref "J2") (pin "36") (pinfunction "H1_36_36") (pintype "bidirectional"))
    )
    (net (code "133") (name "unconnected-(J2-H1_37-Pad37)") (class "Default")
      (node (ref "J2") (pin "37") (pinfunction "H1_37_37") (pintype "bidirectional"))
    )
    (net (code "134") (name "unconnected-(J2-H1_38-Pad38)") (class "Default")
      (node (ref "J2") (pin "38") (pinfunction "H1_38_38") (pintype "bidirectional"))
    )
    (net (code "135") (name "unconnected-(J2-H1_41-Pad41)") (class "Default")
      (node (ref "J2") (pin "41") (pinfunction "H1_41_41") (pintype "bidirectional"))
    )
    (net (code "136") (name "unconnected-(J2-H1_42-Pad42)") (class "Default")
      (node (ref "J2") (pin "42") (pinfunction "H1_42_42") (pintype "bidirectional"))
    )
    (net (code "137") (name "unconnected-(J2-H1_43-Pad43)") (class "Default")
      (node (ref "J2") (pin "43") (pinfunction "H1_43_43") (pintype "bidirectional"))
    )
    (net (code "138") (name "unconnected-(J2-H1_44-Pad44)") (class "Default")
      (node (ref "J2") (pin "44") (pinfunction "H1_44_44") (pintype "bidirectional"))
    )
    (net (code "139") (name "unconnected-(J2-H1_45-Pad45)") (class "Default")
      (node (ref "J2") (pin "45") (pinfunction "H1_45_45") (pintype "bidirectional"))
    )
    (net (code "140") (name "unconnected-(J2-H1_46-Pad46)") (class "Default")
      (node (ref "J2") (pin "46") (pinfunction "H1_46_46") (pintype "bidirectional"))
    )
    (net (code "141") (name "unconnected-(J2-H1_47-Pad47)") (class "Default")
      (node (ref "J2") (pin "47") (pinfunction "H1_47_47") (pintype "bidirectional"))
    )
    (net (code "142") (name "unconnected-(J2-H1_48-Pad48)") (class "Default")
      (node (ref "J2") (pin "48") (pinfunction "H1_48_48") (pintype "bidirectional"))
    )
    (net (code "143") (name "unconnected-(J2-H1_49-Pad49)") (class "Default")
      (node (ref "J2") (pin "49") (pinfunction "H1_49_49") (pintype "bidirectional"))
    )
    (net (code "144") (name "unconnected-(J2-H1_50-Pad50)") (class "Default")
      (node (ref "J2") (pin "50") (pinfunction "H1_50_50") (pintype "bidirectional"))
    )
    (net (code "145") (name "unconnected-(J2-H1_51-Pad51)") (class "Default")
      (node (ref "J2") (pin "51") (pinfunction "H1_51_51") (pintype "bidirectional"))
    )
    (net (code "146") (name "unconnected-(J2-H1_52-Pad52)") (class "Default")
      (node (ref "J2") (pin "52") (pinfunction "H1_52_52") (pintype "bidirectional"))
    )
    (net (code "147") (name "unconnected-(J2-H2_1-Pad53)") (class "Default")
      (node (ref "J2") (pin "53") (pinfunction "H2_1_53") (pintype "bidirectional"))
    )
    (net (code "148") (name "unconnected-(J2-H2_2-Pad54)") (class "Default")
      (node (ref "J2") (pin "54") (pinfunction "H2_2_54") (pintype "bidirectional"))
    )
    (net (code "149") (name "unconnected-(J2-H2_3-Pad55)") (class "Default")
      (node (ref "J2") (pin "55") (pinfunction "H2_3_55") (pintype "bidirectional"))
    )
    (net (code "150") (name "unconnected-(J2-H2_4-Pad56)") (class "Default")
      (node (ref "J2") (pin "56") (pinfunction "H2_4_56") (pintype "bidirectional"))
    )
    (net (code "151") (name "unconnected-(J2-H2_5-Pad57)") (class "Default")
      (node (ref "J2") (pin "57") (pinfunction "H2_5_57") (pintype "bidirectional"))
    )
    (net (code "152") (name "unconnected-(J2-H2_6-Pad58)") (class "Default")
      (node (ref "J2") (pin "58") (pinfunction "H2_6_58") (pintype "bidirectional"))
    )
    (net (code "153") (name "unconnected-(J2-H2_7-Pad59)") (class "Default")
      (node (ref "J2") (pin "59") (pinfunction "H2_7_59") (pintype "bidirectional"))
    )
    (net (code "154") (name "unconnected-(J2-H2_8-Pad60)") (class "Default")
      (node (ref "J2") (pin "60") (pinfunction "H2_8_60") (pintype "bidirectional"))
    )
    (net (code "155") (name "unconnected-(J2-H2_9-Pad61)") (class "Default")
      (node (ref "J2") (pin "61") (pinfunction "H2_9_61") (pintype "bidirectional"))
    )
    (net (code "156") (name "unconnected-(J2-H2_10-Pad62)") (class "Default")
      (node (ref "J2") (pin "62") (pinfunction "H2_10_62") (pintype "bidirectional"))
    )
    (net (code "157") (name "unconnected-(J2-H2_11-Pad63)") (class "Default")
      (node (ref "J2") (pin "63") (pinfunction "H2_11_63") (pintype "bidirectional"))
    )
    (net (code "158") (name "unconnected-(J2-H2_12-Pad64)") (class "Default")
      (node (ref "J2") (pin "64") (pinfunction "H2_12_64") (pintype "bidirectional"))
    )
    (net (code "159") (name "unconnected-(J2-H2_13-Pad65)") (class "Default")
      (node (ref "J2") (pin "65") (pinfunction "H2_13_65") (pintype "bidirectional"))
    )
    (net (code "160") (name "unconnected-(J2-H2_14-Pad66)") (class "Default")
      (node (ref "J2") (pin "66") (pinfunction "H2_14_66") (pintype "bidirectional"))
    )
    (net (code "161") (name "unconnected-(J2-H2_15-Pad67)") (class "Default")
      (node (ref "J2") (pin "67") (pinfunction "H2_15_67") (pintype "bidirectional"))
    )
    (net (code "162") (name "unconnected-(J2-H2_16-Pad68)") (class "Default")
      (node (ref "J2") (pin "68") (pinfunction "H2_16_68") (pintype "bidirectional"))
    )
    (net (code "163") (name "unconnected-(J2-H2_17-Pad69)") (class "Default")
      (node (ref "J2") (pin "69") (pinfunction "H2_17_69") (pintype "bidirectional"))
    )
    (net (code "164") (name "unconnected-(J2-H2_18-Pad70)") (class "Default")
      (node (ref "J2") (pin "70") (pinfunction "H2_18_70") (pintype "bidirectional"))
    )
    (net (code "165") (name "unconnected-(J2-H2_19-Pad71)") (class "Default")
      (node (ref "J2") (pin "71") (pinfunction "H2_19_71") (pintype "bidirectional"))
    )
    (net (code "166") (name "unconnected-(J2-H2_20-Pad72)") (class "Default")
      (node (ref "J2") (pin "72") (pinfunction "H2_20_72") (pintype "bidirectional"))
    )
    (net (code "167") (name "unconnected-(J2-H2_21-Pad73)") (class "Default")
      (node (ref "J2") (pin "73") (pinfunction "H2_21_73") (pintype "bidirectional"))
    )
    (net (code "168") (name "unconnected-(J2-H2_22-Pad74)") (class "Default")
      (node (ref "J2") (pin "74") (pinfunction "H2_22_74") (pintype "bidirectional"))
    )
    (net (code "169") (name "unconnected-(J2-H2_23-Pad75)") (class "Default")
      (node (ref "J2") (pin "75") (pinfunction "H2_23_75") (pintype "bidirectional"))
    )
    (net (code "170") (name "unconnected-(J2-H2_24-Pad76)") (class "Default")
      (node (ref "J2") (pin "76") (pinfunction "H2_24_76") (pintype "bidirectional"))
    )
    (net (code "171") (name "unconnected-(J2-H2_33-Pad85)") (class "Default")
      (node (ref "J2") (pin "85") (pinfunction "H2_33_85") (pintype "bidirectional"))
    )
    (net (code "172") (name "unconnected-(J2-H2_34-Pad86)") (class "Default")
      (node (ref "J2") (pin "86") (pinfunction "H2_34_86") (pintype "bidirectional"))
    )
    (net (code "173") (name "unconnected-(J2-H2_35-Pad87)") (class "Default")
      (node (ref "J2") (pin "87") (pinfunction "H2_35_87") (pintype "bidirectional"))
    )
    (net (code "174") (name "unconnected-(J2-H2_36-Pad88)") (class "Default")
      (node (ref "J2") (pin "88") (pinfunction "H2_36_88") (pintype "bidirectional"))
    )
    (net (code "175") (name "unconnected-(J2-H2_37-Pad89)") (class "Default")
      (node (ref "J2") (pin "89") (pinfunction "H2_37_89") (pintype "bidirectional"))
    )
    (net (code "176") (name "unconnected-(J2-H2_38-Pad90)") (class "Default")
      (node (ref "J2") (pin "90") (pinfunction "H2_38_90") (pintype "bidirectional"))
    )
    (net (code "177") (name "unconnected-(J2-H2_39-Pad91)") (class "Default")
      (node (ref "J2") (pin "91") (pinfunction "H2_39_91") (pintype "bidirectional"))
    )
    (net (code "178") (name "unconnected-(J2-H2_40-Pad92)") (class "Default")
      (node (ref "J2") (pin "92") (pinfunction "H2_40_92") (pintype "bidirectional"))
    )
    (net (code "179") (name "unconnected-(J2-H2_41-Pad93)") (class "Default")
      (node (ref "J2") (pin "93") (pinfunction "H2_41_93") (pintype "bidirectional"))
    )
    (net (code "180") (name "unconnected-(J2-H2_42-Pad94)") (class "Default")
      (node (ref "J2") (pin "94") (pinfunction "H2_42_94") (pintype "bidirectional"))
    )
    (net (code "181") (name "unconnected-(J2-H2_43-Pad95)") (class "Default")
      (node (ref "J2") (pin "95") (pinfunction "H2_43_95") (pintype "bidirectional"))
    )
    (net (code "182") (name "unconnected-(J2-H2_44-Pad96)") (class "Default")
      (node (ref "J2") (pin "96") (pinfunction "H2_44_96") (pintype "bidirectional"))
    )
    (net (code "183") (name "unconnected-(J2-H2_47-Pad99)") (class "Default")
      (node (ref "J2") (pin "99") (pinfunction "H2_47_99") (pintype "bidirectional"))
    )
    (net (code "184") (name "unconnected-(J2-H2_48-Pad100)") (class "Default")
      (node (ref "J2") (pin "100") (pinfunction "H2_48_100") (pintype "bidirectional"))
    )
    (net (code "185") (name "unconnected-(J2-H2_49-Pad101)") (class "Default")
      (node (ref "J2") (pin "101") (pinfunction "H2_49_101") (pintype "bidirectional"))
    )
    (net (code "186") (name "unconnected-(J2-H2_50-Pad102)") (class "Default")
      (node (ref "J2") (pin "102") (pinfunction "H2_50_102") (pintype "bidirectional"))
    )
    (net (code "187") (name "unconnected-(J2-H2_51-Pad103)") (class "Default")
      (node (ref "J2") (pin "103") (pinfunction "H2_51_103") (pintype "bidirectional"))
    )
    (net (code "188") (name "unconnected-(J2-H2_52-Pad104)") (class "Default")
      (node (ref "J2") (pin "104") (pinfunction "H2_52_104") (pintype "bidirectional"))
    )
    (net (code "189") (name "unconnected-(U1-PD7-Pad10)") (class "Default")
      (node (ref "U1") (pin "10") (pinfunction "PD7_10") (pintype "bidirectional"))
    )
    (net (code "190") (name "unconnected-(U1-PF4-Pad5)") (class "Default")
      (node (ref "U1") (pin "5") (pinfunction "PF4_5") (pintype "bidirectional"))
    )
    (net (code "191") (name "unconnected-(U6-A2-Pad4)") (class "Default")
      (node (ref "U6") (pin "4") (pinfunction "A2_4") (pintype "bidirectional"))
    )
    (net (code "192") (name "unconnected-(U6-B2-Pad1)") (class "Default")
      (node (ref "U6") (pin "1") (pinfunction "B2_1") (pintype "bidirectional"))
    )
    (net (code "193") (name "~{HIB}") (class "Default")
      (node (ref "TP17") (pin "TP") (pinfunction "TP_TP") (pintype "input"))
      (node (ref "U1") (pin "33") (pinfunction "HIB_N_33") (pintype "output"))
    )
    (net (code "194") (name "~{RST}") (class "Default")
      (node (ref "C13") (pin "1") (pinfunction "1_1") (pintype "passive"))
      (node (ref "J1") (pin "10") (pinfunction "10_10") (pintype "bidirectional"))
      (node (ref "R2") (pin "2") (pinfunction "2_2") (pintype "passive"))
      (node (ref "S1") (pin "1") (pinfunction "S_1") (pintype "passive"))
      (node (ref "S1") (pin "2") (pinfunction "S1_2") (pintype "passive"))
      (node (ref "U1") (pin "38") (pinfunction "RST_N_38") (pintype "input"))
    )
    (net (code "195") (name "~{SS}") (class "Default")
      (node (ref "D5") (pin "2") (pinfunction "2_2") (pintype "bidirectional"))
      (node (ref "J9") (pin "2") (pinfunction "DATA3/CD_2") (pintype "bidirectional"))
      (node (ref "R15") (pin "1") (pinfunction "1_1") (pintype "passive"))
      (node (ref "U1") (pin "20") (pinfunction "PA3_SSI0FSS_20") (pintype "bidirectional"))
    )
  )
)
